# avraic.net
KiCad netlist of a schematic drawn in EAGLE
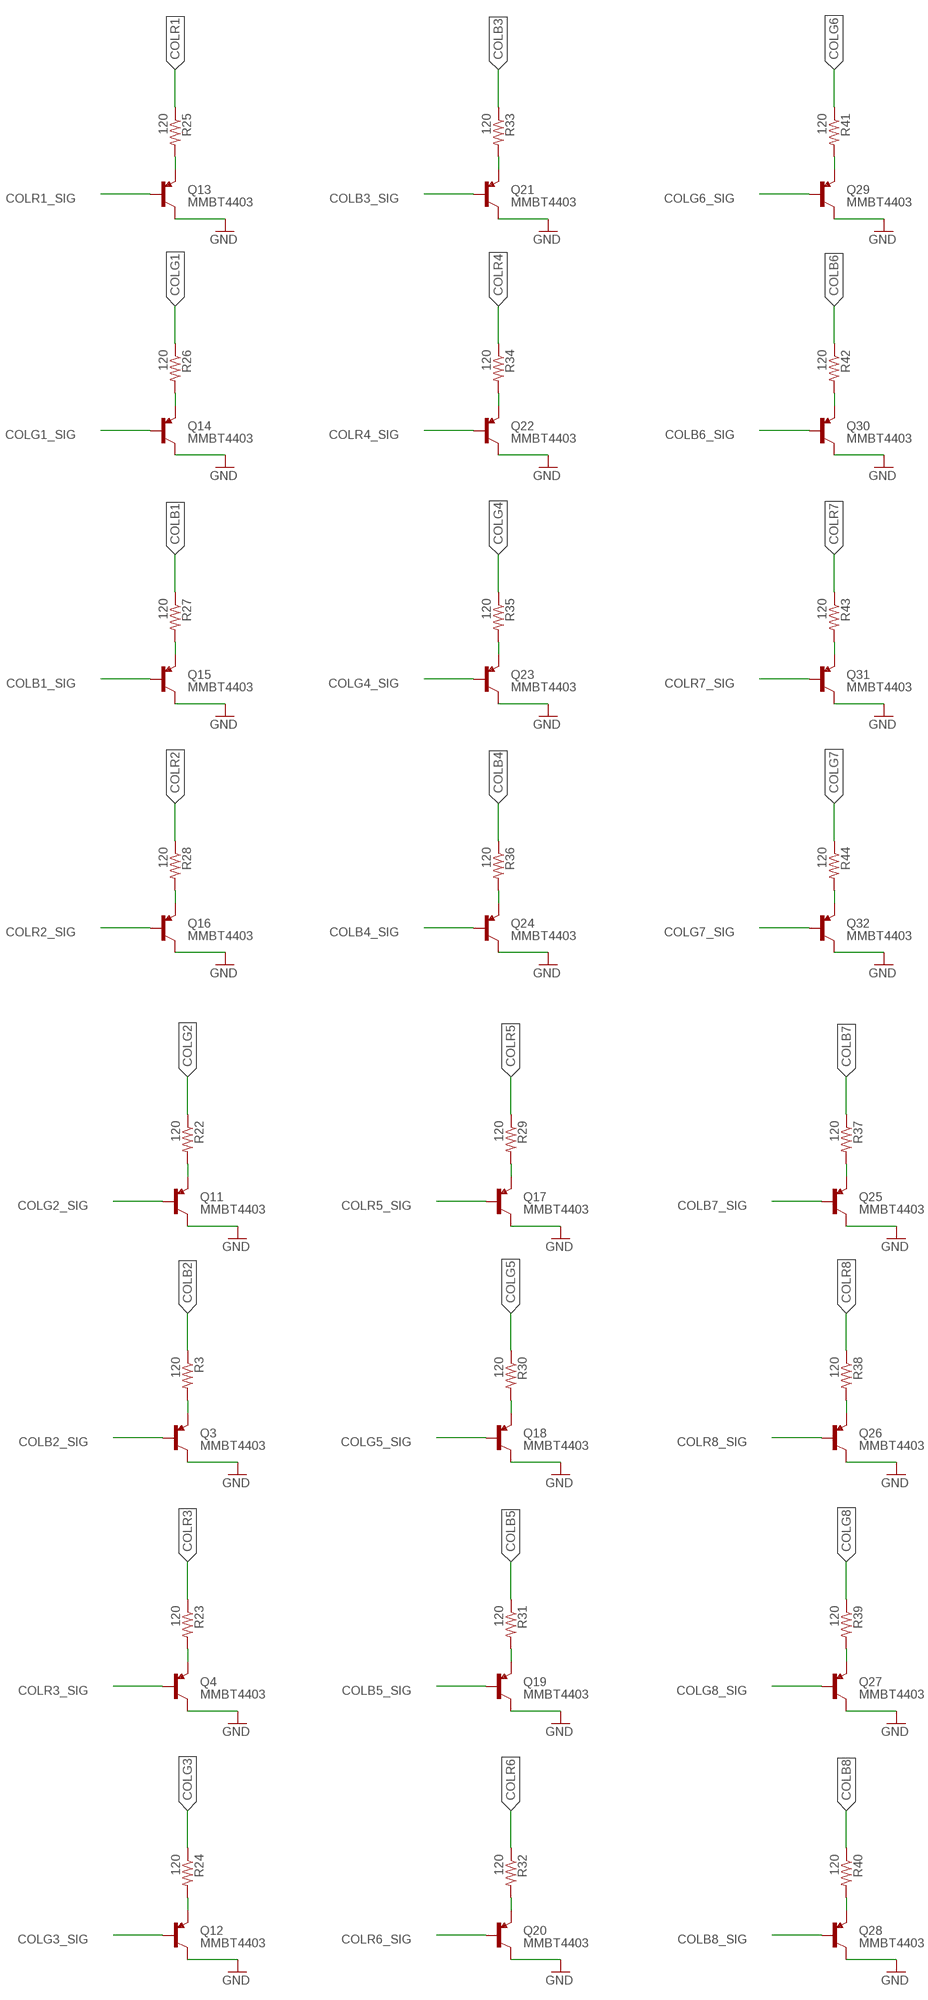
[diagram p0: schematic, sheet 1, part 1 of 3]
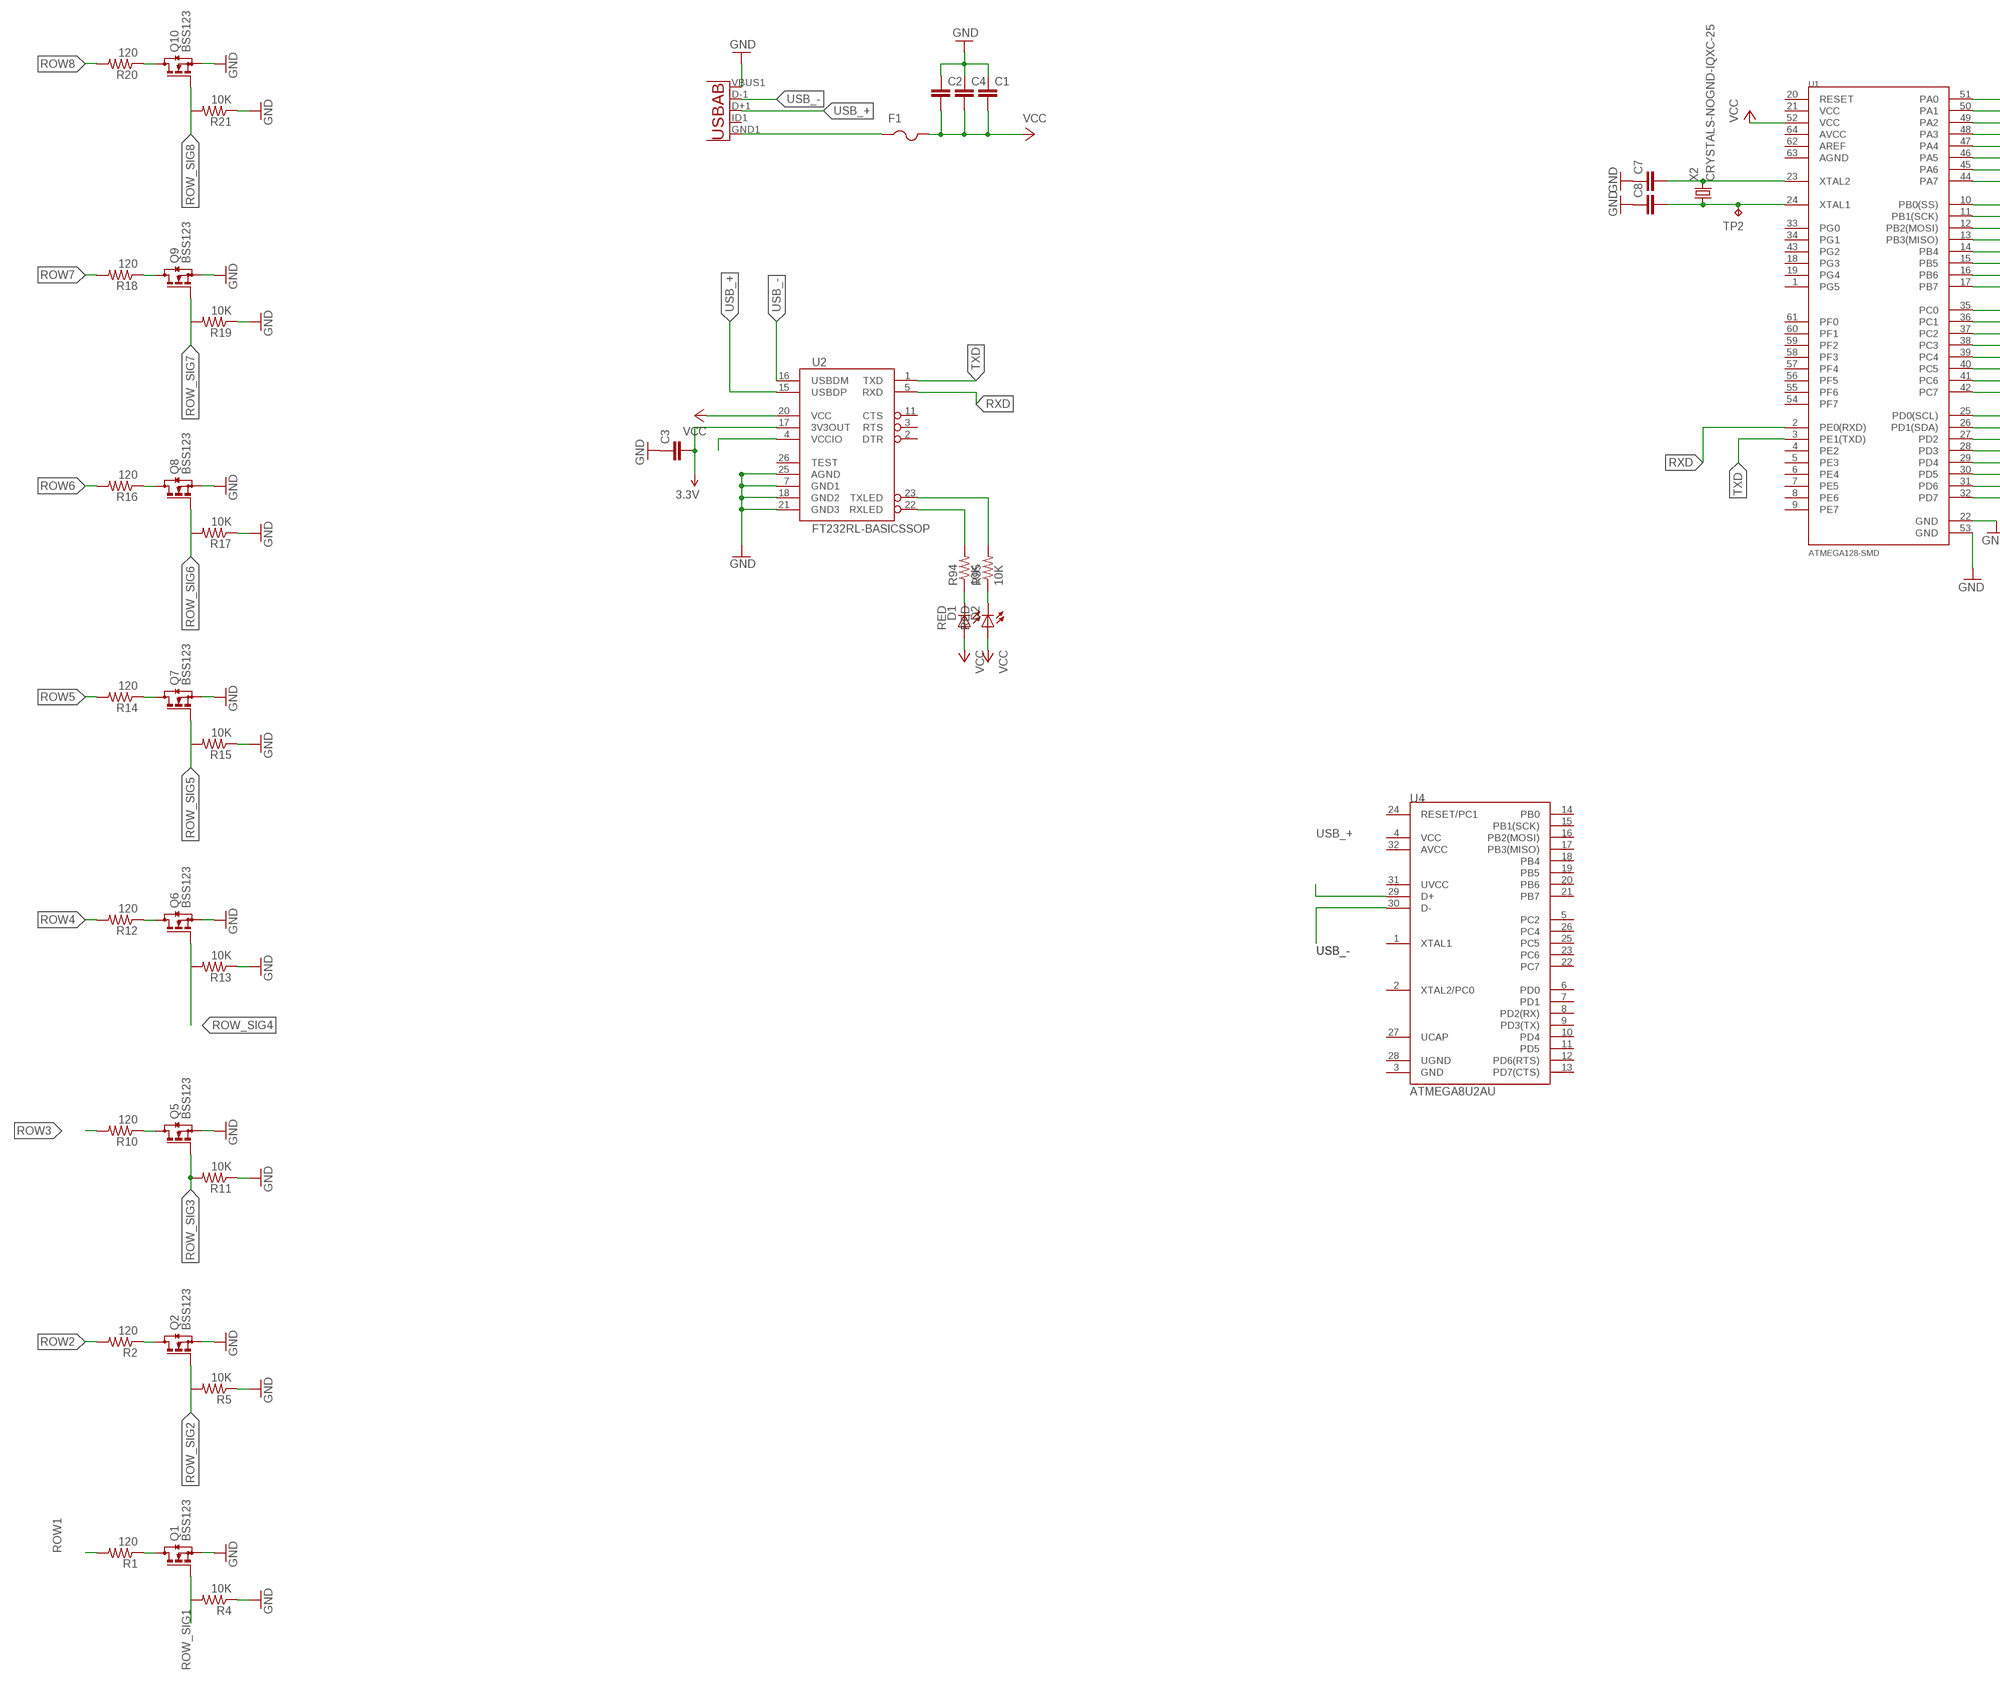
[diagram p1: schematic, sheet 1, part 2 of 3]
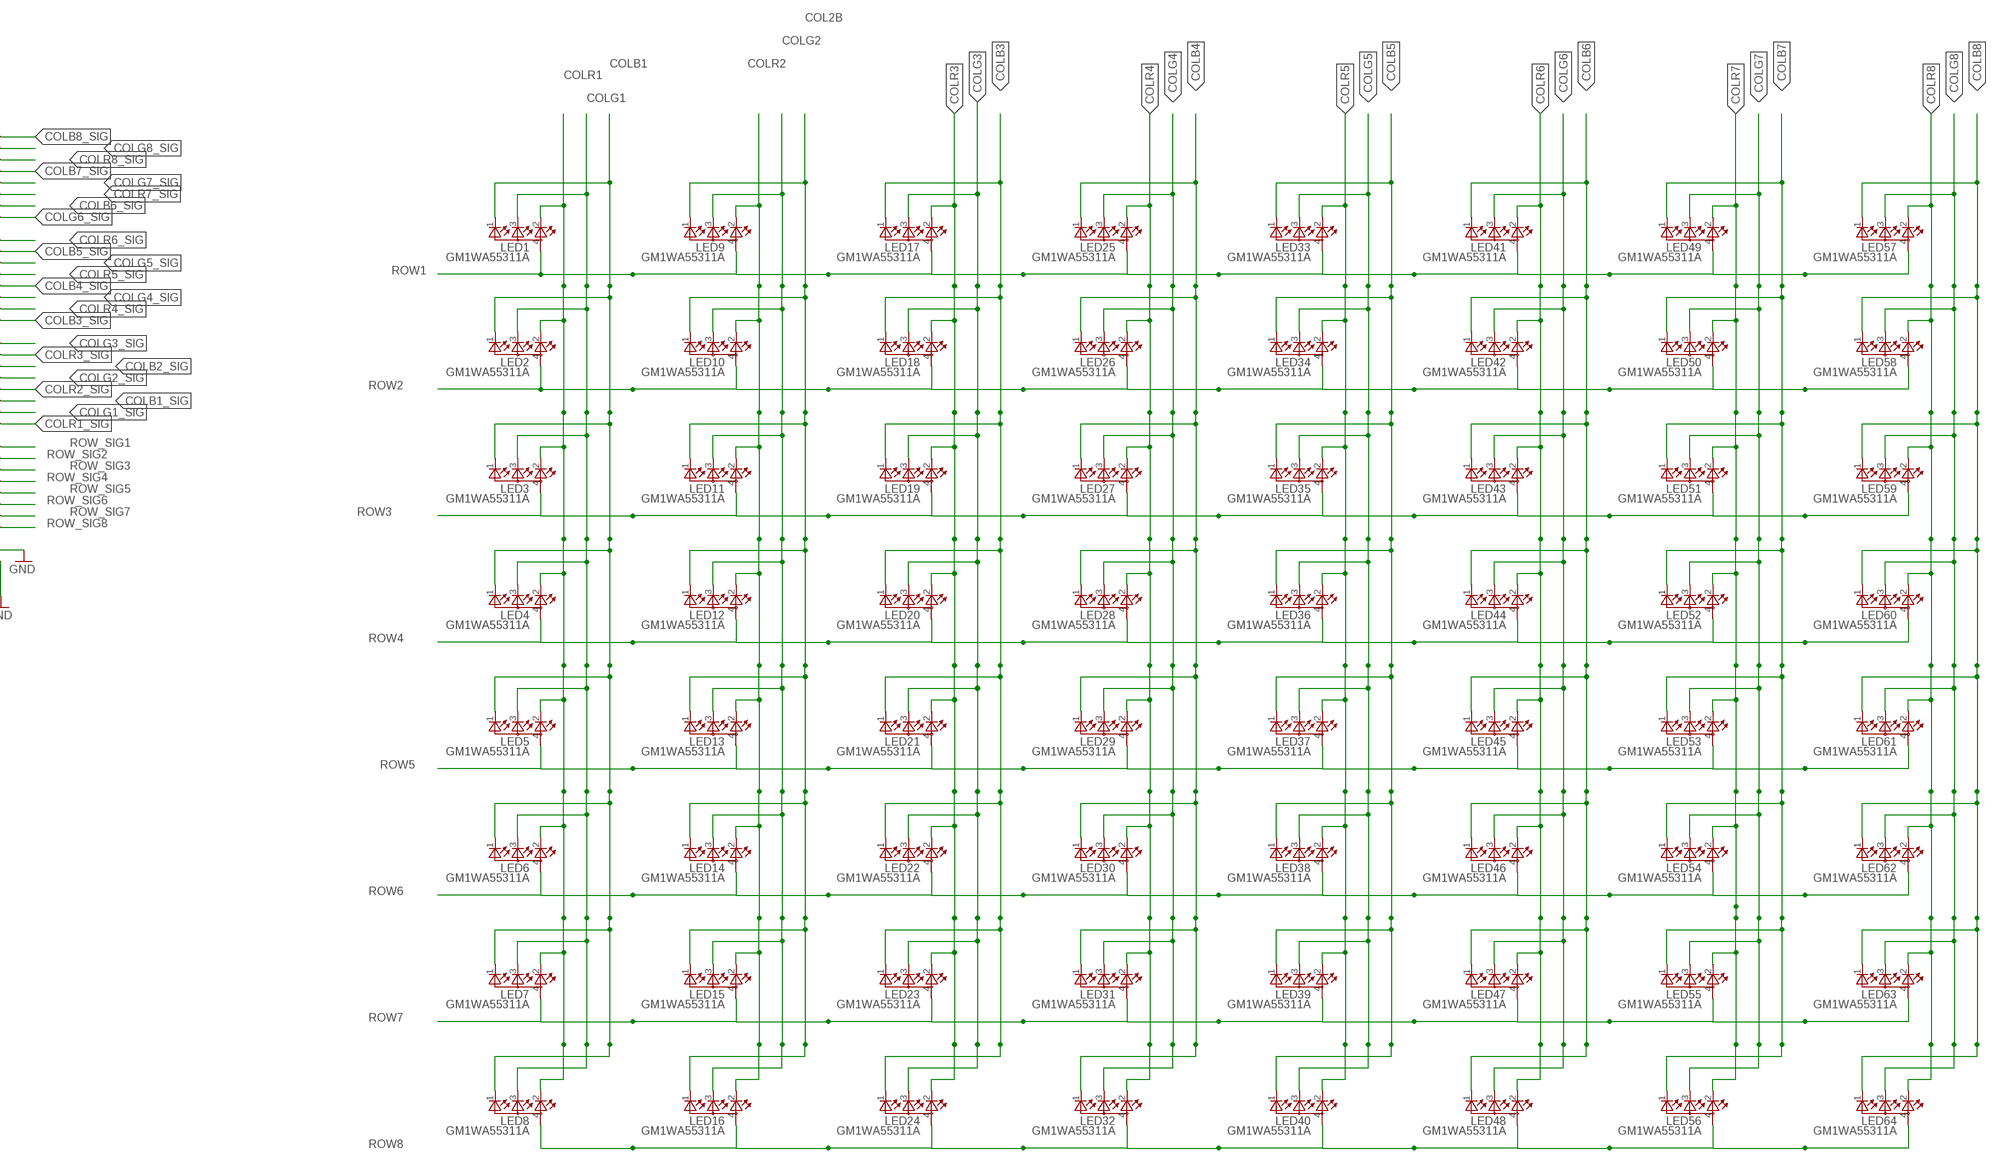
[diagram p2: schematic, sheet 1, part 3 of 3]

(export (version "E")
  (design (tool "Eeschema 10.0.6"))
  (components
    (comp (ref "C1")
      (value "C-EUC0201")
      (footprint "eagle-import:C0201")
      (libsource (lib "eagle-import") (part "C-EUC0201"))
    )
    (comp (ref "C2")
      (value "C-EUC0201")
      (footprint "eagle-import:C0201")
      (libsource (lib "eagle-import") (part "C-EUC0201"))
    )
    (comp (ref "C3")
      (value "C-EUC0402K")
      (footprint "eagle-import:C0402K")
      (libsource (lib "eagle-import") (part "C-EUC0402K"))
    )
    (comp (ref "C4")
      (value "C-EUC0201")
      (footprint "eagle-import:C0201")
      (libsource (lib "eagle-import") (part "C-EUC0201"))
    )
    (comp (ref "C7")
      (value "C-EUC0402K")
      (footprint "eagle-import:C0402K")
      (libsource (lib "eagle-import") (part "C-EUC0402K"))
    )
    (comp (ref "C8")
      (value "C-EUC0402K")
      (footprint "eagle-import:C0402K")
      (libsource (lib "eagle-import") (part "C-EUC0402K"))
    )
    (comp (ref "D1")
      (value "RED")
      (footprint "eagle-import:CHIP-LED0603")
      (libsource (lib "eagle-import") (part "LEDCHIP-LED0603"))
    )
    (comp (ref "D2")
      (value "RED")
      (footprint "eagle-import:CHIP-LED0603")
      (libsource (lib "eagle-import") (part "LEDCHIP-LED0603"))
    )
    (comp (ref "F1")
      (value "PTCFUSE-1206")
      (footprint "eagle-import:R1206")
      (libsource (lib "eagle-import") (part "PTCFUSE-1206"))
    )
    (comp (ref "LED1")
      (value "GM1WA55311A")
      (footprint "eagle-import:GM1WA55311A")
      (libsource (lib "eagle-import") (part "GM1WA55311A"))
    )
    (comp (ref "LED2")
      (value "GM1WA55311A")
      (footprint "eagle-import:GM1WA55311A")
      (libsource (lib "eagle-import") (part "GM1WA55311A"))
    )
    (comp (ref "LED3")
      (value "GM1WA55311A")
      (footprint "eagle-import:GM1WA55311A")
      (libsource (lib "eagle-import") (part "GM1WA55311A"))
    )
    (comp (ref "LED4")
      (value "GM1WA55311A")
      (footprint "eagle-import:GM1WA55311A")
      (libsource (lib "eagle-import") (part "GM1WA55311A"))
    )
    (comp (ref "LED5")
      (value "GM1WA55311A")
      (footprint "eagle-import:GM1WA55311A")
      (libsource (lib "eagle-import") (part "GM1WA55311A"))
    )
    (comp (ref "LED6")
      (value "GM1WA55311A")
      (footprint "eagle-import:GM1WA55311A")
      (libsource (lib "eagle-import") (part "GM1WA55311A"))
    )
    (comp (ref "LED7")
      (value "GM1WA55311A")
      (footprint "eagle-import:GM1WA55311A")
      (libsource (lib "eagle-import") (part "GM1WA55311A"))
    )
    (comp (ref "LED8")
      (value "GM1WA55311A")
      (footprint "eagle-import:GM1WA55311A")
      (libsource (lib "eagle-import") (part "GM1WA55311A"))
    )
    (comp (ref "LED9")
      (value "GM1WA55311A")
      (footprint "eagle-import:GM1WA55311A")
      (libsource (lib "eagle-import") (part "GM1WA55311A"))
    )
    (comp (ref "LED10")
      (value "GM1WA55311A")
      (footprint "eagle-import:GM1WA55311A")
      (libsource (lib "eagle-import") (part "GM1WA55311A"))
    )
    (comp (ref "LED11")
      (value "GM1WA55311A")
      (footprint "eagle-import:GM1WA55311A")
      (libsource (lib "eagle-import") (part "GM1WA55311A"))
    )
    (comp (ref "LED12")
      (value "GM1WA55311A")
      (footprint "eagle-import:GM1WA55311A")
      (libsource (lib "eagle-import") (part "GM1WA55311A"))
    )
    (comp (ref "LED13")
      (value "GM1WA55311A")
      (footprint "eagle-import:GM1WA55311A")
      (libsource (lib "eagle-import") (part "GM1WA55311A"))
    )
    (comp (ref "LED14")
      (value "GM1WA55311A")
      (footprint "eagle-import:GM1WA55311A")
      (libsource (lib "eagle-import") (part "GM1WA55311A"))
    )
    (comp (ref "LED15")
      (value "GM1WA55311A")
      (footprint "eagle-import:GM1WA55311A")
      (libsource (lib "eagle-import") (part "GM1WA55311A"))
    )
    (comp (ref "LED16")
      (value "GM1WA55311A")
      (footprint "eagle-import:GM1WA55311A")
      (libsource (lib "eagle-import") (part "GM1WA55311A"))
    )
    (comp (ref "LED17")
      (value "GM1WA55311A")
      (footprint "eagle-import:GM1WA55311A")
      (libsource (lib "eagle-import") (part "GM1WA55311A"))
    )
    (comp (ref "LED18")
      (value "GM1WA55311A")
      (footprint "eagle-import:GM1WA55311A")
      (libsource (lib "eagle-import") (part "GM1WA55311A"))
    )
    (comp (ref "LED19")
      (value "GM1WA55311A")
      (footprint "eagle-import:GM1WA55311A")
      (libsource (lib "eagle-import") (part "GM1WA55311A"))
    )
    (comp (ref "LED20")
      (value "GM1WA55311A")
      (footprint "eagle-import:GM1WA55311A")
      (libsource (lib "eagle-import") (part "GM1WA55311A"))
    )
    (comp (ref "LED21")
      (value "GM1WA55311A")
      (footprint "eagle-import:GM1WA55311A")
      (libsource (lib "eagle-import") (part "GM1WA55311A"))
    )
    (comp (ref "LED22")
      (value "GM1WA55311A")
      (footprint "eagle-import:GM1WA55311A")
      (libsource (lib "eagle-import") (part "GM1WA55311A"))
    )
    (comp (ref "LED23")
      (value "GM1WA55311A")
      (footprint "eagle-import:GM1WA55311A")
      (libsource (lib "eagle-import") (part "GM1WA55311A"))
    )
    (comp (ref "LED24")
      (value "GM1WA55311A")
      (footprint "eagle-import:GM1WA55311A")
      (libsource (lib "eagle-import") (part "GM1WA55311A"))
    )
    (comp (ref "LED25")
      (value "GM1WA55311A")
      (footprint "eagle-import:GM1WA55311A")
      (libsource (lib "eagle-import") (part "GM1WA55311A"))
    )
    (comp (ref "LED26")
      (value "GM1WA55311A")
      (footprint "eagle-import:GM1WA55311A")
      (libsource (lib "eagle-import") (part "GM1WA55311A"))
    )
    (comp (ref "LED27")
      (value "GM1WA55311A")
      (footprint "eagle-import:GM1WA55311A")
      (libsource (lib "eagle-import") (part "GM1WA55311A"))
    )
    (comp (ref "LED28")
      (value "GM1WA55311A")
      (footprint "eagle-import:GM1WA55311A")
      (libsource (lib "eagle-import") (part "GM1WA55311A"))
    )
    (comp (ref "LED29")
      (value "GM1WA55311A")
      (footprint "eagle-import:GM1WA55311A")
      (libsource (lib "eagle-import") (part "GM1WA55311A"))
    )
    (comp (ref "LED30")
      (value "GM1WA55311A")
      (footprint "eagle-import:GM1WA55311A")
      (libsource (lib "eagle-import") (part "GM1WA55311A"))
    )
    (comp (ref "LED31")
      (value "GM1WA55311A")
      (footprint "eagle-import:GM1WA55311A")
      (libsource (lib "eagle-import") (part "GM1WA55311A"))
    )
    (comp (ref "LED32")
      (value "GM1WA55311A")
      (footprint "eagle-import:GM1WA55311A")
      (libsource (lib "eagle-import") (part "GM1WA55311A"))
    )
    (comp (ref "LED33")
      (value "GM1WA55311A")
      (footprint "eagle-import:GM1WA55311A")
      (libsource (lib "eagle-import") (part "GM1WA55311A"))
    )
    (comp (ref "LED34")
      (value "GM1WA55311A")
      (footprint "eagle-import:GM1WA55311A")
      (libsource (lib "eagle-import") (part "GM1WA55311A"))
    )
    (comp (ref "LED35")
      (value "GM1WA55311A")
      (footprint "eagle-import:GM1WA55311A")
      (libsource (lib "eagle-import") (part "GM1WA55311A"))
    )
    (comp (ref "LED36")
      (value "GM1WA55311A")
      (footprint "eagle-import:GM1WA55311A")
      (libsource (lib "eagle-import") (part "GM1WA55311A"))
    )
    (comp (ref "LED37")
      (value "GM1WA55311A")
      (footprint "eagle-import:GM1WA55311A")
      (libsource (lib "eagle-import") (part "GM1WA55311A"))
    )
    (comp (ref "LED38")
      (value "GM1WA55311A")
      (footprint "eagle-import:GM1WA55311A")
      (libsource (lib "eagle-import") (part "GM1WA55311A"))
    )
    (comp (ref "LED39")
      (value "GM1WA55311A")
      (footprint "eagle-import:GM1WA55311A")
      (libsource (lib "eagle-import") (part "GM1WA55311A"))
    )
    (comp (ref "LED40")
      (value "GM1WA55311A")
      (footprint "eagle-import:GM1WA55311A")
      (libsource (lib "eagle-import") (part "GM1WA55311A"))
    )
    (comp (ref "LED41")
      (value "GM1WA55311A")
      (footprint "eagle-import:GM1WA55311A")
      (libsource (lib "eagle-import") (part "GM1WA55311A"))
    )
    (comp (ref "LED42")
      (value "GM1WA55311A")
      (footprint "eagle-import:GM1WA55311A")
      (libsource (lib "eagle-import") (part "GM1WA55311A"))
    )
    (comp (ref "LED43")
      (value "GM1WA55311A")
      (footprint "eagle-import:GM1WA55311A")
      (libsource (lib "eagle-import") (part "GM1WA55311A"))
    )
    (comp (ref "LED44")
      (value "GM1WA55311A")
      (footprint "eagle-import:GM1WA55311A")
      (libsource (lib "eagle-import") (part "GM1WA55311A"))
    )
    (comp (ref "LED45")
      (value "GM1WA55311A")
      (footprint "eagle-import:GM1WA55311A")
      (libsource (lib "eagle-import") (part "GM1WA55311A"))
    )
    (comp (ref "LED46")
      (value "GM1WA55311A")
      (footprint "eagle-import:GM1WA55311A")
      (libsource (lib "eagle-import") (part "GM1WA55311A"))
    )
    (comp (ref "LED47")
      (value "GM1WA55311A")
      (footprint "eagle-import:GM1WA55311A")
      (libsource (lib "eagle-import") (part "GM1WA55311A"))
    )
    (comp (ref "LED48")
      (value "GM1WA55311A")
      (footprint "eagle-import:GM1WA55311A")
      (libsource (lib "eagle-import") (part "GM1WA55311A"))
    )
    (comp (ref "LED49")
      (value "GM1WA55311A")
      (footprint "eagle-import:GM1WA55311A")
      (libsource (lib "eagle-import") (part "GM1WA55311A"))
    )
    (comp (ref "LED50")
      (value "GM1WA55311A")
      (footprint "eagle-import:GM1WA55311A")
      (libsource (lib "eagle-import") (part "GM1WA55311A"))
    )
    (comp (ref "LED51")
      (value "GM1WA55311A")
      (footprint "eagle-import:GM1WA55311A")
      (libsource (lib "eagle-import") (part "GM1WA55311A"))
    )
    (comp (ref "LED52")
      (value "GM1WA55311A")
      (footprint "eagle-import:GM1WA55311A")
      (libsource (lib "eagle-import") (part "GM1WA55311A"))
    )
    (comp (ref "LED53")
      (value "GM1WA55311A")
      (footprint "eagle-import:GM1WA55311A")
      (libsource (lib "eagle-import") (part "GM1WA55311A"))
    )
    (comp (ref "LED54")
      (value "GM1WA55311A")
      (footprint "eagle-import:GM1WA55311A")
      (libsource (lib "eagle-import") (part "GM1WA55311A"))
    )
    (comp (ref "LED55")
      (value "GM1WA55311A")
      (footprint "eagle-import:GM1WA55311A")
      (libsource (lib "eagle-import") (part "GM1WA55311A"))
    )
    (comp (ref "LED56")
      (value "GM1WA55311A")
      (footprint "eagle-import:GM1WA55311A")
      (libsource (lib "eagle-import") (part "GM1WA55311A"))
    )
    (comp (ref "LED57")
      (value "GM1WA55311A")
      (footprint "eagle-import:GM1WA55311A")
      (libsource (lib "eagle-import") (part "GM1WA55311A"))
    )
    (comp (ref "LED58")
      (value "GM1WA55311A")
      (footprint "eagle-import:GM1WA55311A")
      (libsource (lib "eagle-import") (part "GM1WA55311A"))
    )
    (comp (ref "LED59")
      (value "GM1WA55311A")
      (footprint "eagle-import:GM1WA55311A")
      (libsource (lib "eagle-import") (part "GM1WA55311A"))
    )
    (comp (ref "LED60")
      (value "GM1WA55311A")
      (footprint "eagle-import:GM1WA55311A")
      (libsource (lib "eagle-import") (part "GM1WA55311A"))
    )
    (comp (ref "LED61")
      (value "GM1WA55311A")
      (footprint "eagle-import:GM1WA55311A")
      (libsource (lib "eagle-import") (part "GM1WA55311A"))
    )
    (comp (ref "LED62")
      (value "GM1WA55311A")
      (footprint "eagle-import:GM1WA55311A")
      (libsource (lib "eagle-import") (part "GM1WA55311A"))
    )
    (comp (ref "LED63")
      (value "GM1WA55311A")
      (footprint "eagle-import:GM1WA55311A")
      (libsource (lib "eagle-import") (part "GM1WA55311A"))
    )
    (comp (ref "LED64")
      (value "GM1WA55311A")
      (footprint "eagle-import:GM1WA55311A")
      (libsource (lib "eagle-import") (part "GM1WA55311A"))
    )
    (comp (ref "Q1")
      (value "BSS123")
      (footprint "eagle-import:SOT23")
      (libsource (lib "eagle-import") (part "BSS123"))
    )
    (comp (ref "Q2")
      (value "BSS123")
      (footprint "eagle-import:SOT23")
      (libsource (lib "eagle-import") (part "BSS123"))
    )
    (comp (ref "Q3")
      (value "MMBT4403")
      (footprint "eagle-import:SOT23-3")
      (libsource (lib "eagle-import") (part "TRANSISTOR_PNPMMBT4403"))
    )
    (comp (ref "Q4")
      (value "MMBT4403")
      (footprint "eagle-import:SOT23-3")
      (libsource (lib "eagle-import") (part "TRANSISTOR_PNPMMBT4403"))
    )
    (comp (ref "Q5")
      (value "BSS123")
      (footprint "eagle-import:SOT23")
      (libsource (lib "eagle-import") (part "BSS123"))
    )
    (comp (ref "Q6")
      (value "BSS123")
      (footprint "eagle-import:SOT23")
      (libsource (lib "eagle-import") (part "BSS123"))
    )
    (comp (ref "Q7")
      (value "BSS123")
      (footprint "eagle-import:SOT23")
      (libsource (lib "eagle-import") (part "BSS123"))
    )
    (comp (ref "Q8")
      (value "BSS123")
      (footprint "eagle-import:SOT23")
      (libsource (lib "eagle-import") (part "BSS123"))
    )
    (comp (ref "Q9")
      (value "BSS123")
      (footprint "eagle-import:SOT23")
      (libsource (lib "eagle-import") (part "BSS123"))
    )
    (comp (ref "Q10")
      (value "BSS123")
      (footprint "eagle-import:SOT23")
      (libsource (lib "eagle-import") (part "BSS123"))
    )
    (comp (ref "Q11")
      (value "MMBT4403")
      (footprint "eagle-import:SOT23-3")
      (libsource (lib "eagle-import") (part "TRANSISTOR_PNPMMBT4403"))
    )
    (comp (ref "Q12")
      (value "MMBT4403")
      (footprint "eagle-import:SOT23-3")
      (libsource (lib "eagle-import") (part "TRANSISTOR_PNPMMBT4403"))
    )
    (comp (ref "Q13")
      (value "MMBT4403")
      (footprint "eagle-import:SOT23-3")
      (libsource (lib "eagle-import") (part "TRANSISTOR_PNPMMBT4403"))
    )
    (comp (ref "Q14")
      (value "MMBT4403")
      (footprint "eagle-import:SOT23-3")
      (libsource (lib "eagle-import") (part "TRANSISTOR_PNPMMBT4403"))
    )
    (comp (ref "Q15")
      (value "MMBT4403")
      (footprint "eagle-import:SOT23-3")
      (libsource (lib "eagle-import") (part "TRANSISTOR_PNPMMBT4403"))
    )
    (comp (ref "Q16")
      (value "MMBT4403")
      (footprint "eagle-import:SOT23-3")
      (libsource (lib "eagle-import") (part "TRANSISTOR_PNPMMBT4403"))
    )
    (comp (ref "Q17")
      (value "MMBT4403")
      (footprint "eagle-import:SOT23-3")
      (libsource (lib "eagle-import") (part "TRANSISTOR_PNPMMBT4403"))
    )
    (comp (ref "Q18")
      (value "MMBT4403")
      (footprint "eagle-import:SOT23-3")
      (libsource (lib "eagle-import") (part "TRANSISTOR_PNPMMBT4403"))
    )
    (comp (ref "Q19")
      (value "MMBT4403")
      (footprint "eagle-import:SOT23-3")
      (libsource (lib "eagle-import") (part "TRANSISTOR_PNPMMBT4403"))
    )
    (comp (ref "Q20")
      (value "MMBT4403")
      (footprint "eagle-import:SOT23-3")
      (libsource (lib "eagle-import") (part "TRANSISTOR_PNPMMBT4403"))
    )
    (comp (ref "Q21")
      (value "MMBT4403")
      (footprint "eagle-import:SOT23-3")
      (libsource (lib "eagle-import") (part "TRANSISTOR_PNPMMBT4403"))
    )
    (comp (ref "Q22")
      (value "MMBT4403")
      (footprint "eagle-import:SOT23-3")
      (libsource (lib "eagle-import") (part "TRANSISTOR_PNPMMBT4403"))
    )
    (comp (ref "Q23")
      (value "MMBT4403")
      (footprint "eagle-import:SOT23-3")
      (libsource (lib "eagle-import") (part "TRANSISTOR_PNPMMBT4403"))
    )
    (comp (ref "Q24")
      (value "MMBT4403")
      (footprint "eagle-import:SOT23-3")
      (libsource (lib "eagle-import") (part "TRANSISTOR_PNPMMBT4403"))
    )
    (comp (ref "Q25")
      (value "MMBT4403")
      (footprint "eagle-import:SOT23-3")
      (libsource (lib "eagle-import") (part "TRANSISTOR_PNPMMBT4403"))
    )
    (comp (ref "Q26")
      (value "MMBT4403")
      (footprint "eagle-import:SOT23-3")
      (libsource (lib "eagle-import") (part "TRANSISTOR_PNPMMBT4403"))
    )
    (comp (ref "Q27")
      (value "MMBT4403")
      (footprint "eagle-import:SOT23-3")
      (libsource (lib "eagle-import") (part "TRANSISTOR_PNPMMBT4403"))
    )
    (comp (ref "Q28")
      (value "MMBT4403")
      (footprint "eagle-import:SOT23-3")
      (libsource (lib "eagle-import") (part "TRANSISTOR_PNPMMBT4403"))
    )
    (comp (ref "Q29")
      (value "MMBT4403")
      (footprint "eagle-import:SOT23-3")
      (libsource (lib "eagle-import") (part "TRANSISTOR_PNPMMBT4403"))
    )
    (comp (ref "Q30")
      (value "MMBT4403")
      (footprint "eagle-import:SOT23-3")
      (libsource (lib "eagle-import") (part "TRANSISTOR_PNPMMBT4403"))
    )
    (comp (ref "Q31")
      (value "MMBT4403")
      (footprint "eagle-import:SOT23-3")
      (libsource (lib "eagle-import") (part "TRANSISTOR_PNPMMBT4403"))
    )
    (comp (ref "Q32")
      (value "MMBT4403")
      (footprint "eagle-import:SOT23-3")
      (libsource (lib "eagle-import") (part "TRANSISTOR_PNPMMBT4403"))
    )
    (comp (ref "R1")
      (value "120")
      (footprint "eagle-import:0603-RES")
      (libsource (lib "eagle-import") (part "RESISTOR0603-RES"))
    )
    (comp (ref "R2")
      (value "120")
      (footprint "eagle-import:0603-RES")
      (libsource (lib "eagle-import") (part "RESISTOR0603-RES"))
    )
    (comp (ref "R3")
      (value "120")
      (footprint "eagle-import:MINI_MELF-0102R")
      (libsource (lib "eagle-import") (part "R-US_MELF0102R"))
    )
    (comp (ref "R4")
      (value "10K")
      (footprint "eagle-import:0603-RES")
      (libsource (lib "eagle-import") (part "RESISTOR0603-RES"))
    )
    (comp (ref "R5")
      (value "10K")
      (footprint "eagle-import:0603-RES")
      (libsource (lib "eagle-import") (part "RESISTOR0603-RES"))
    )
    (comp (ref "R10")
      (value "120")
      (footprint "eagle-import:0603-RES")
      (libsource (lib "eagle-import") (part "RESISTOR0603-RES"))
    )
    (comp (ref "R11")
      (value "10K")
      (footprint "eagle-import:0603-RES")
      (libsource (lib "eagle-import") (part "RESISTOR0603-RES"))
    )
    (comp (ref "R12")
      (value "120")
      (footprint "eagle-import:0603-RES")
      (libsource (lib "eagle-import") (part "RESISTOR0603-RES"))
    )
    (comp (ref "R13")
      (value "10K")
      (footprint "eagle-import:0603-RES")
      (libsource (lib "eagle-import") (part "RESISTOR0603-RES"))
    )
    (comp (ref "R14")
      (value "120")
      (footprint "eagle-import:0603-RES")
      (libsource (lib "eagle-import") (part "RESISTOR0603-RES"))
    )
    (comp (ref "R15")
      (value "10K")
      (footprint "eagle-import:0603-RES")
      (libsource (lib "eagle-import") (part "RESISTOR0603-RES"))
    )
    (comp (ref "R16")
      (value "120")
      (footprint "eagle-import:0603-RES")
      (libsource (lib "eagle-import") (part "RESISTOR0603-RES"))
    )
    (comp (ref "R17")
      (value "10K")
      (footprint "eagle-import:0603-RES")
      (libsource (lib "eagle-import") (part "RESISTOR0603-RES"))
    )
    (comp (ref "R18")
      (value "120")
      (footprint "eagle-import:0603-RES")
      (libsource (lib "eagle-import") (part "RESISTOR0603-RES"))
    )
    (comp (ref "R19")
      (value "10K")
      (footprint "eagle-import:0603-RES")
      (libsource (lib "eagle-import") (part "RESISTOR0603-RES"))
    )
    (comp (ref "R20")
      (value "120")
      (footprint "eagle-import:0603-RES")
      (libsource (lib "eagle-import") (part "RESISTOR0603-RES"))
    )
    (comp (ref "R21")
      (value "10K")
      (footprint "eagle-import:0603-RES")
      (libsource (lib "eagle-import") (part "RESISTOR0603-RES"))
    )
    (comp (ref "R22")
      (value "120")
      (footprint "eagle-import:MINI_MELF-0102R")
      (libsource (lib "eagle-import") (part "R-US_MELF0102R"))
    )
    (comp (ref "R23")
      (value "120")
      (footprint "eagle-import:MINI_MELF-0102R")
      (libsource (lib "eagle-import") (part "R-US_MELF0102R"))
    )
    (comp (ref "R24")
      (value "120")
      (footprint "eagle-import:0603-RES")
      (libsource (lib "eagle-import") (part "RESISTOR0603-RES"))
    )
    (comp (ref "R25")
      (value "120")
      (footprint "eagle-import:0603-RES")
      (libsource (lib "eagle-import") (part "RESISTOR0603-RES"))
    )
    (comp (ref "R26")
      (value "120")
      (footprint "eagle-import:MINI_MELF-0102R")
      (libsource (lib "eagle-import") (part "R-US_MELF0102R"))
    )
    (comp (ref "R27")
      (value "120")
      (footprint "eagle-import:MINI_MELF-0102R")
      (libsource (lib "eagle-import") (part "R-US_MELF0102R"))
    )
    (comp (ref "R28")
      (value "120")
      (footprint "eagle-import:MINI_MELF-0102R")
      (libsource (lib "eagle-import") (part "R-US_MELF0102R"))
    )
    (comp (ref "R29")
      (value "120")
      (footprint "eagle-import:MINI_MELF-0102R")
      (libsource (lib "eagle-import") (part "R-US_MELF0102R"))
    )
    (comp (ref "R30")
      (value "120")
      (footprint "eagle-import:0603-RES")
      (libsource (lib "eagle-import") (part "RESISTOR0603-RES"))
    )
    (comp (ref "R31")
      (value "120")
      (footprint "eagle-import:0603-RES")
      (libsource (lib "eagle-import") (part "RESISTOR0603-RES"))
    )
    (comp (ref "R32")
      (value "120")
      (footprint "eagle-import:0603-RES")
      (libsource (lib "eagle-import") (part "RESISTOR0603-RES"))
    )
    (comp (ref "R33")
      (value "120")
      (footprint "eagle-import:MINI_MELF-0102R")
      (libsource (lib "eagle-import") (part "R-US_MELF0102R"))
    )
    (comp (ref "R34")
      (value "120")
      (footprint "eagle-import:MINI_MELF-0102R")
      (libsource (lib "eagle-import") (part "R-US_MELF0102R"))
    )
    (comp (ref "R35")
      (value "120")
      (footprint "eagle-import:MINI_MELF-0102R")
      (libsource (lib "eagle-import") (part "R-US_MELF0102R"))
    )
    (comp (ref "R36")
      (value "120")
      (footprint "eagle-import:MINI_MELF-0102R")
      (libsource (lib "eagle-import") (part "R-US_MELF0102R"))
    )
    (comp (ref "R37")
      (value "120")
      (footprint "eagle-import:MINI_MELF-0102R")
      (libsource (lib "eagle-import") (part "R-US_MELF0102R"))
    )
    (comp (ref "R38")
      (value "120")
      (footprint "eagle-import:MINI_MELF-0102R")
      (libsource (lib "eagle-import") (part "R-US_MELF0102R"))
    )
    (comp (ref "R39")
      (value "120")
      (footprint "eagle-import:MINI_MELF-0102R")
      (libsource (lib "eagle-import") (part "R-US_MELF0102R"))
    )
    (comp (ref "R40")
      (value "120")
      (footprint "eagle-import:MINI_MELF-0102R")
      (libsource (lib "eagle-import") (part "R-US_MELF0102R"))
    )
    (comp (ref "R41")
      (value "120")
      (footprint "eagle-import:MINI_MELF-0102R")
      (libsource (lib "eagle-import") (part "R-US_MELF0102R"))
    )
    (comp (ref "R42")
      (value "120")
      (footprint "eagle-import:MINI_MELF-0102R")
      (libsource (lib "eagle-import") (part "R-US_MELF0102R"))
    )
    (comp (ref "R43")
      (value "120")
      (footprint "eagle-import:MINI_MELF-0102R")
      (libsource (lib "eagle-import") (part "R-US_MELF0102R"))
    )
    (comp (ref "R44")
      (value "120")
      (footprint "eagle-import:MINI_MELF-0102R")
      (libsource (lib "eagle-import") (part "R-US_MELF0102R"))
    )
    (comp (ref "R94")
      (value "10K")
      (footprint "eagle-import:0603-RES")
      (libsource (lib "eagle-import") (part "RESISTOR0603-RES"))
    )
    (comp (ref "R95")
      (value "10K")
      (footprint "eagle-import:0603-RES")
      (libsource (lib "eagle-import") (part "RESISTOR0603-RES"))
    )
    (comp (ref "TP2")
      (value "TPB1,27")
      (footprint "eagle-import:B1,27")
      (libsource (lib "eagle-import") (part "TPB1,27"))
    )
    (comp (ref "U1")
      (value "ATMEGA128-SMD")
      (footprint "eagle-import:TQFP64_14X14MM")
      (libsource (lib "eagle-import") (part "ATMEGA128-SMD"))
    )
    (comp (ref "U2")
      (value "FT232RL-BASICSSOP")
      (footprint "eagle-import:SSOP28DB")
      (libsource (lib "eagle-import") (part "FT232RL-BASICSSOP"))
    )
    (comp (ref "U3")
      (value "USB\"\"")
      (footprint "eagle-import:USB-MICRO-SMD")
      (libsource (lib "eagle-import") (part "USB{dblquote}{dblquote}"))
    )
    (comp (ref "U4")
      (value "ATMEGA8U2AU")
      (footprint "eagle-import:TQFP32-08")
      (libsource (lib "eagle-import") (part "ATMEGA8U2AU"))
    )
    (comp (ref "X2")
      (value "CRYSTALS-NOGND-IQXC-25")
      (footprint "eagle-import:2.0X1.2-2PAD")
      (libsource (lib "eagle-import") (part "CRYSTALS-NOGND-IQXC-25"))
    )
  )
  (nets
    (net (code "1") (name "/COL2B") (class "Default")
      (node (ref "LED10") (pin "1") (pinfunction "CGREEN_1") (pintype "passive"))
      (node (ref "LED11") (pin "1") (pinfunction "CGREEN_1") (pintype "passive"))
      (node (ref "LED12") (pin "1") (pinfunction "CGREEN_1") (pintype "passive"))
      (node (ref "LED13") (pin "1") (pinfunction "CGREEN_1") (pintype "passive"))
      (node (ref "LED14") (pin "1") (pinfunction "CGREEN_1") (pintype "passive"))
      (node (ref "LED15") (pin "1") (pinfunction "CGREEN_1") (pintype "passive"))
      (node (ref "LED16") (pin "1") (pinfunction "CGREEN_1") (pintype "passive"))
      (node (ref "LED9") (pin "1") (pinfunction "CGREEN_1") (pintype "passive"))
    )
    (net (code "2") (name "/ROW1") (class "Default")
      (node (ref "LED1") (pin "4") (pinfunction "A_4") (pintype "passive"))
      (node (ref "LED17") (pin "4") (pinfunction "A_4") (pintype "passive"))
      (node (ref "LED25") (pin "4") (pinfunction "A_4") (pintype "passive"))
      (node (ref "LED33") (pin "4") (pinfunction "A_4") (pintype "passive"))
      (node (ref "LED41") (pin "4") (pinfunction "A_4") (pintype "passive"))
      (node (ref "LED49") (pin "4") (pinfunction "A_4") (pintype "passive"))
      (node (ref "LED57") (pin "4") (pinfunction "A_4") (pintype "passive"))
      (node (ref "LED9") (pin "4") (pinfunction "A_4") (pintype "passive"))
      (node (ref "R1") (pin "2") (pinfunction "2_2") (pintype "passive"))
    )
    (net (code "3") (name "/ROW_SIG1") (class "Default")
      (node (ref "Q1") (pin "1") (pinfunction "G_1") (pintype "passive"))
      (node (ref "R4") (pin "2") (pinfunction "2_2") (pintype "passive"))
      (node (ref "U1") (pin "25") (pinfunction "PD0(SCL)_25") (pintype "bidirectional"))
    )
    (net (code "4") (name "3.3V") (class "Default")
      (node (ref "C3") (pin "2") (pinfunction "2_2") (pintype "passive"))
      (node (ref "U2") (pin "17") (pinfunction "3V3OUT_17") (pintype "output"))
    )
    (net (code "5") (name "COLB1") (class "Default")
      (node (ref "LED1") (pin "1") (pinfunction "CGREEN_1") (pintype "passive"))
      (node (ref "LED2") (pin "1") (pinfunction "CGREEN_1") (pintype "passive"))
      (node (ref "LED3") (pin "1") (pinfunction "CGREEN_1") (pintype "passive"))
      (node (ref "LED4") (pin "1") (pinfunction "CGREEN_1") (pintype "passive"))
      (node (ref "LED5") (pin "1") (pinfunction "CGREEN_1") (pintype "passive"))
      (node (ref "LED6") (pin "1") (pinfunction "CGREEN_1") (pintype "passive"))
      (node (ref "LED7") (pin "1") (pinfunction "CGREEN_1") (pintype "passive"))
      (node (ref "LED8") (pin "1") (pinfunction "CGREEN_1") (pintype "passive"))
      (node (ref "R27") (pin "1") (pinfunction "1_1") (pintype "passive"))
    )
    (net (code "6") (name "COLB1_SIG") (class "Default")
      (node (ref "Q15") (pin "1") (pinfunction "B_1") (pintype "passive"))
      (node (ref "U1") (pin "40") (pinfunction "PC5_40") (pintype "bidirectional"))
    )
    (net (code "7") (name "COLB2") (class "Default")
      (node (ref "R3") (pin "1") (pinfunction "1_1") (pintype "passive"))
    )
    (net (code "8") (name "COLB2_SIG") (class "Default")
      (node (ref "Q3") (pin "1") (pinfunction "B_1") (pintype "passive"))
      (node (ref "U1") (pin "37") (pinfunction "PC2_37") (pintype "bidirectional"))
    )
    (net (code "9") (name "COLB3") (class "Default")
      (node (ref "LED17") (pin "1") (pinfunction "CGREEN_1") (pintype "passive"))
      (node (ref "LED18") (pin "1") (pinfunction "CGREEN_1") (pintype "passive"))
      (node (ref "LED19") (pin "1") (pinfunction "CGREEN_1") (pintype "passive"))
      (node (ref "LED20") (pin "1") (pinfunction "CGREEN_1") (pintype "passive"))
      (node (ref "LED21") (pin "1") (pinfunction "CGREEN_1") (pintype "passive"))
      (node (ref "LED22") (pin "1") (pinfunction "CGREEN_1") (pintype "passive"))
      (node (ref "LED23") (pin "1") (pinfunction "CGREEN_1") (pintype "passive"))
      (node (ref "LED24") (pin "1") (pinfunction "CGREEN_1") (pintype "passive"))
      (node (ref "R33") (pin "1") (pinfunction "1_1") (pintype "passive"))
    )
    (net (code "10") (name "COLB3_SIG") (class "Default")
      (node (ref "Q21") (pin "1") (pinfunction "B_1") (pintype "passive"))
      (node (ref "U1") (pin "17") (pinfunction "PB7_17") (pintype "bidirectional"))
    )
    (net (code "11") (name "COLB4") (class "Default")
      (node (ref "LED25") (pin "1") (pinfunction "CGREEN_1") (pintype "passive"))
      (node (ref "LED26") (pin "1") (pinfunction "CGREEN_1") (pintype "passive"))
      (node (ref "LED27") (pin "1") (pinfunction "CGREEN_1") (pintype "passive"))
      (node (ref "LED28") (pin "1") (pinfunction "CGREEN_1") (pintype "passive"))
      (node (ref "LED29") (pin "1") (pinfunction "CGREEN_1") (pintype "passive"))
      (node (ref "LED30") (pin "1") (pinfunction "CGREEN_1") (pintype "passive"))
      (node (ref "LED31") (pin "1") (pinfunction "CGREEN_1") (pintype "passive"))
      (node (ref "LED32") (pin "1") (pinfunction "CGREEN_1") (pintype "passive"))
      (node (ref "R36") (pin "1") (pinfunction "1_1") (pintype "passive"))
    )
    (net (code "12") (name "COLB4_SIG") (class "Default")
      (node (ref "Q24") (pin "1") (pinfunction "B_1") (pintype "passive"))
      (node (ref "U1") (pin "14") (pinfunction "PB4_14") (pintype "bidirectional"))
    )
    (net (code "13") (name "COLB5") (class "Default")
      (node (ref "LED33") (pin "1") (pinfunction "CGREEN_1") (pintype "passive"))
      (node (ref "LED34") (pin "1") (pinfunction "CGREEN_1") (pintype "passive"))
      (node (ref "LED35") (pin "1") (pinfunction "CGREEN_1") (pintype "passive"))
      (node (ref "LED36") (pin "1") (pinfunction "CGREEN_1") (pintype "passive"))
      (node (ref "LED37") (pin "1") (pinfunction "CGREEN_1") (pintype "passive"))
      (node (ref "LED38") (pin "1") (pinfunction "CGREEN_1") (pintype "passive"))
      (node (ref "LED39") (pin "1") (pinfunction "CGREEN_1") (pintype "passive"))
      (node (ref "LED40") (pin "1") (pinfunction "CGREEN_1") (pintype "passive"))
      (node (ref "R31") (pin "1") (pinfunction "1_1") (pintype "passive"))
    )
    (net (code "14") (name "COLB5_SIG") (class "Default")
      (node (ref "Q19") (pin "1") (pinfunction "B_1") (pintype "passive"))
      (node (ref "U1") (pin "11") (pinfunction "PB1(SCK)_11") (pintype "bidirectional"))
    )
    (net (code "15") (name "COLB6") (class "Default")
      (node (ref "LED41") (pin "1") (pinfunction "CGREEN_1") (pintype "passive"))
      (node (ref "LED42") (pin "1") (pinfunction "CGREEN_1") (pintype "passive"))
      (node (ref "LED43") (pin "1") (pinfunction "CGREEN_1") (pintype "passive"))
      (node (ref "LED44") (pin "1") (pinfunction "CGREEN_1") (pintype "passive"))
      (node (ref "LED45") (pin "1") (pinfunction "CGREEN_1") (pintype "passive"))
      (node (ref "LED46") (pin "1") (pinfunction "CGREEN_1") (pintype "passive"))
      (node (ref "LED47") (pin "1") (pinfunction "CGREEN_1") (pintype "passive"))
      (node (ref "LED48") (pin "1") (pinfunction "CGREEN_1") (pintype "passive"))
      (node (ref "R42") (pin "1") (pinfunction "1_1") (pintype "passive"))
    )
    (net (code "16") (name "COLB6_SIG") (class "Default")
      (node (ref "Q30") (pin "1") (pinfunction "B_1") (pintype "passive"))
      (node (ref "U1") (pin "45") (pinfunction "PA6_45") (pintype "bidirectional"))
    )
    (net (code "17") (name "COLB7") (class "Default")
      (node (ref "LED49") (pin "1") (pinfunction "CGREEN_1") (pintype "passive"))
      (node (ref "LED50") (pin "1") (pinfunction "CGREEN_1") (pintype "passive"))
      (node (ref "LED51") (pin "1") (pinfunction "CGREEN_1") (pintype "passive"))
      (node (ref "LED52") (pin "1") (pinfunction "CGREEN_1") (pintype "passive"))
      (node (ref "LED53") (pin "1") (pinfunction "CGREEN_1") (pintype "passive"))
      (node (ref "LED54") (pin "1") (pinfunction "CGREEN_1") (pintype "passive"))
      (node (ref "LED55") (pin "1") (pinfunction "CGREEN_1") (pintype "passive"))
      (node (ref "LED56") (pin "1") (pinfunction "CGREEN_1") (pintype "passive"))
      (node (ref "R37") (pin "1") (pinfunction "1_1") (pintype "passive"))
    )
    (net (code "18") (name "COLB7_SIG") (class "Default")
      (node (ref "Q25") (pin "1") (pinfunction "B_1") (pintype "passive"))
      (node (ref "U1") (pin "48") (pinfunction "PA3_48") (pintype "bidirectional"))
    )
    (net (code "19") (name "COLB8") (class "Default")
      (node (ref "LED57") (pin "1") (pinfunction "CGREEN_1") (pintype "passive"))
      (node (ref "LED58") (pin "1") (pinfunction "CGREEN_1") (pintype "passive"))
      (node (ref "LED59") (pin "1") (pinfunction "CGREEN_1") (pintype "passive"))
      (node (ref "LED60") (pin "1") (pinfunction "CGREEN_1") (pintype "passive"))
      (node (ref "LED61") (pin "1") (pinfunction "CGREEN_1") (pintype "passive"))
      (node (ref "LED62") (pin "1") (pinfunction "CGREEN_1") (pintype "passive"))
      (node (ref "LED63") (pin "1") (pinfunction "CGREEN_1") (pintype "passive"))
      (node (ref "LED64") (pin "1") (pinfunction "CGREEN_1") (pintype "passive"))
      (node (ref "R40") (pin "1") (pinfunction "1_1") (pintype "passive"))
    )
    (net (code "20") (name "COLB8_SIG") (class "Default")
      (node (ref "Q28") (pin "1") (pinfunction "B_1") (pintype "passive"))
      (node (ref "U1") (pin "51") (pinfunction "PA0_51") (pintype "bidirectional"))
    )
    (net (code "21") (name "COLG1") (class "Default")
      (node (ref "LED1") (pin "3") (pinfunction "CBLUE_3") (pintype "passive"))
      (node (ref "LED2") (pin "3") (pinfunction "CBLUE_3") (pintype "passive"))
      (node (ref "LED3") (pin "3") (pinfunction "CBLUE_3") (pintype "passive"))
      (node (ref "LED4") (pin "3") (pinfunction "CBLUE_3") (pintype "passive"))
      (node (ref "LED5") (pin "3") (pinfunction "CBLUE_3") (pintype "passive"))
      (node (ref "LED6") (pin "3") (pinfunction "CBLUE_3") (pintype "passive"))
      (node (ref "LED7") (pin "3") (pinfunction "CBLUE_3") (pintype "passive"))
      (node (ref "LED8") (pin "3") (pinfunction "CBLUE_3") (pintype "passive"))
      (node (ref "R26") (pin "1") (pinfunction "1_1") (pintype "passive"))
    )
    (net (code "22") (name "COLG1_SIG") (class "Default")
      (node (ref "Q14") (pin "1") (pinfunction "B_1") (pintype "passive"))
      (node (ref "U1") (pin "41") (pinfunction "PC6_41") (pintype "bidirectional"))
    )
    (net (code "23") (name "COLG2") (class "Default")
      (node (ref "LED10") (pin "3") (pinfunction "CBLUE_3") (pintype "passive"))
      (node (ref "LED11") (pin "3") (pinfunction "CBLUE_3") (pintype "passive"))
      (node (ref "LED12") (pin "3") (pinfunction "CBLUE_3") (pintype "passive"))
      (node (ref "LED13") (pin "3") (pinfunction "CBLUE_3") (pintype "passive"))
      (node (ref "LED14") (pin "3") (pinfunction "CBLUE_3") (pintype "passive"))
      (node (ref "LED15") (pin "3") (pinfunction "CBLUE_3") (pintype "passive"))
      (node (ref "LED16") (pin "3") (pinfunction "CBLUE_3") (pintype "passive"))
      (node (ref "LED9") (pin "3") (pinfunction "CBLUE_3") (pintype "passive"))
      (node (ref "R22") (pin "1") (pinfunction "1_1") (pintype "passive"))
    )
    (net (code "24") (name "COLG2_SIG") (class "Default")
      (node (ref "Q11") (pin "1") (pinfunction "B_1") (pintype "passive"))
      (node (ref "U1") (pin "38") (pinfunction "PC3_38") (pintype "bidirectional"))
    )
    (net (code "25") (name "COLG3") (class "Default")
      (node (ref "LED17") (pin "3") (pinfunction "CBLUE_3") (pintype "passive"))
      (node (ref "LED18") (pin "3") (pinfunction "CBLUE_3") (pintype "passive"))
      (node (ref "LED19") (pin "3") (pinfunction "CBLUE_3") (pintype "passive"))
      (node (ref "LED20") (pin "3") (pinfunction "CBLUE_3") (pintype "passive"))
      (node (ref "LED21") (pin "3") (pinfunction "CBLUE_3") (pintype "passive"))
      (node (ref "LED22") (pin "3") (pinfunction "CBLUE_3") (pintype "passive"))
      (node (ref "LED23") (pin "3") (pinfunction "CBLUE_3") (pintype "passive"))
      (node (ref "LED24") (pin "3") (pinfunction "CBLUE_3") (pintype "passive"))
      (node (ref "R24") (pin "1") (pinfunction "1_1") (pintype "passive"))
    )
    (net (code "26") (name "COLG3_SIG") (class "Default")
      (node (ref "Q12") (pin "1") (pinfunction "B_1") (pintype "passive"))
      (node (ref "U1") (pin "35") (pinfunction "PC0_35") (pintype "bidirectional"))
    )
    (net (code "27") (name "COLG4") (class "Default")
      (node (ref "LED25") (pin "3") (pinfunction "CBLUE_3") (pintype "passive"))
      (node (ref "LED26") (pin "3") (pinfunction "CBLUE_3") (pintype "passive"))
      (node (ref "LED27") (pin "3") (pinfunction "CBLUE_3") (pintype "passive"))
      (node (ref "LED28") (pin "3") (pinfunction "CBLUE_3") (pintype "passive"))
      (node (ref "LED29") (pin "3") (pinfunction "CBLUE_3") (pintype "passive"))
      (node (ref "LED30") (pin "3") (pinfunction "CBLUE_3") (pintype "passive"))
      (node (ref "LED31") (pin "3") (pinfunction "CBLUE_3") (pintype "passive"))
      (node (ref "LED32") (pin "3") (pinfunction "CBLUE_3") (pintype "passive"))
      (node (ref "R35") (pin "1") (pinfunction "1_1") (pintype "passive"))
    )
    (net (code "28") (name "COLG4_SIG") (class "Default")
      (node (ref "Q23") (pin "1") (pinfunction "B_1") (pintype "passive"))
      (node (ref "U1") (pin "15") (pinfunction "PB5_15") (pintype "bidirectional"))
    )
    (net (code "29") (name "COLG5") (class "Default")
      (node (ref "LED33") (pin "3") (pinfunction "CBLUE_3") (pintype "passive"))
      (node (ref "LED34") (pin "3") (pinfunction "CBLUE_3") (pintype "passive"))
      (node (ref "LED35") (pin "3") (pinfunction "CBLUE_3") (pintype "passive"))
      (node (ref "LED36") (pin "3") (pinfunction "CBLUE_3") (pintype "passive"))
      (node (ref "LED37") (pin "3") (pinfunction "CBLUE_3") (pintype "passive"))
      (node (ref "LED38") (pin "3") (pinfunction "CBLUE_3") (pintype "passive"))
      (node (ref "LED39") (pin "3") (pinfunction "CBLUE_3") (pintype "passive"))
      (node (ref "LED40") (pin "3") (pinfunction "CBLUE_3") (pintype "passive"))
      (node (ref "R30") (pin "1") (pinfunction "1_1") (pintype "passive"))
    )
    (net (code "30") (name "COLG5_SIG") (class "Default")
      (node (ref "Q18") (pin "1") (pinfunction "B_1") (pintype "passive"))
      (node (ref "U1") (pin "12") (pinfunction "PB2(MOSI)_12") (pintype "bidirectional"))
    )
    (net (code "31") (name "COLG6") (class "Default")
      (node (ref "LED41") (pin "3") (pinfunction "CBLUE_3") (pintype "passive"))
      (node (ref "LED42") (pin "3") (pinfunction "CBLUE_3") (pintype "passive"))
      (node (ref "LED43") (pin "3") (pinfunction "CBLUE_3") (pintype "passive"))
      (node (ref "LED44") (pin "3") (pinfunction "CBLUE_3") (pintype "passive"))
      (node (ref "LED45") (pin "3") (pinfunction "CBLUE_3") (pintype "passive"))
      (node (ref "LED46") (pin "3") (pinfunction "CBLUE_3") (pintype "passive"))
      (node (ref "LED47") (pin "3") (pinfunction "CBLUE_3") (pintype "passive"))
      (node (ref "LED48") (pin "3") (pinfunction "CBLUE_3") (pintype "passive"))
      (node (ref "R41") (pin "1") (pinfunction "1_1") (pintype "passive"))
    )
    (net (code "32") (name "COLG6_SIG") (class "Default")
      (node (ref "Q29") (pin "1") (pinfunction "B_1") (pintype "passive"))
      (node (ref "U1") (pin "44") (pinfunction "PA7_44") (pintype "bidirectional"))
    )
    (net (code "33") (name "COLG7") (class "Default")
      (node (ref "LED49") (pin "3") (pinfunction "CBLUE_3") (pintype "passive"))
      (node (ref "LED50") (pin "3") (pinfunction "CBLUE_3") (pintype "passive"))
      (node (ref "LED51") (pin "3") (pinfunction "CBLUE_3") (pintype "passive"))
      (node (ref "LED52") (pin "3") (pinfunction "CBLUE_3") (pintype "passive"))
      (node (ref "LED53") (pin "3") (pinfunction "CBLUE_3") (pintype "passive"))
      (node (ref "LED54") (pin "3") (pinfunction "CBLUE_3") (pintype "passive"))
      (node (ref "LED55") (pin "3") (pinfunction "CBLUE_3") (pintype "passive"))
      (node (ref "LED56") (pin "3") (pinfunction "CBLUE_3") (pintype "passive"))
      (node (ref "R44") (pin "1") (pinfunction "1_1") (pintype "passive"))
    )
    (net (code "34") (name "COLG7_SIG") (class "Default")
      (node (ref "Q32") (pin "1") (pinfunction "B_1") (pintype "passive"))
      (node (ref "U1") (pin "47") (pinfunction "PA4_47") (pintype "bidirectional"))
    )
    (net (code "35") (name "COLG8") (class "Default")
      (node (ref "LED57") (pin "3") (pinfunction "CBLUE_3") (pintype "passive"))
      (node (ref "LED58") (pin "3") (pinfunction "CBLUE_3") (pintype "passive"))
      (node (ref "LED59") (pin "3") (pinfunction "CBLUE_3") (pintype "passive"))
      (node (ref "LED60") (pin "3") (pinfunction "CBLUE_3") (pintype "passive"))
      (node (ref "LED61") (pin "3") (pinfunction "CBLUE_3") (pintype "passive"))
      (node (ref "LED62") (pin "3") (pinfunction "CBLUE_3") (pintype "passive"))
      (node (ref "LED63") (pin "3") (pinfunction "CBLUE_3") (pintype "passive"))
      (node (ref "LED64") (pin "3") (pinfunction "CBLUE_3") (pintype "passive"))
      (node (ref "R39") (pin "1") (pinfunction "1_1") (pintype "passive"))
    )
    (net (code "36") (name "COLG8_SIG") (class "Default")
      (node (ref "Q27") (pin "1") (pinfunction "B_1") (pintype "passive"))
      (node (ref "U1") (pin "50") (pinfunction "PA1_50") (pintype "bidirectional"))
    )
    (net (code "37") (name "COLR1") (class "Default")
      (node (ref "LED1") (pin "2") (pinfunction "CRED_2") (pintype "passive"))
      (node (ref "LED2") (pin "2") (pinfunction "CRED_2") (pintype "passive"))
      (node (ref "LED3") (pin "2") (pinfunction "CRED_2") (pintype "passive"))
      (node (ref "LED4") (pin "2") (pinfunction "CRED_2") (pintype "passive"))
      (node (ref "LED5") (pin "2") (pinfunction "CRED_2") (pintype "passive"))
      (node (ref "LED6") (pin "2") (pinfunction "CRED_2") (pintype "passive"))
      (node (ref "LED7") (pin "2") (pinfunction "CRED_2") (pintype "passive"))
      (node (ref "LED8") (pin "2") (pinfunction "CRED_2") (pintype "passive"))
      (node (ref "R25") (pin "1") (pinfunction "1_1") (pintype "passive"))
    )
    (net (code "38") (name "COLR1_SIG") (class "Default")
      (node (ref "Q13") (pin "1") (pinfunction "B_1") (pintype "passive"))
      (node (ref "U1") (pin "42") (pinfunction "PC7_42") (pintype "bidirectional"))
    )
    (net (code "39") (name "COLR2") (class "Default")
      (node (ref "LED10") (pin "2") (pinfunction "CRED_2") (pintype "passive"))
      (node (ref "LED11") (pin "2") (pinfunction "CRED_2") (pintype "passive"))
      (node (ref "LED12") (pin "2") (pinfunction "CRED_2") (pintype "passive"))
      (node (ref "LED13") (pin "2") (pinfunction "CRED_2") (pintype "passive"))
      (node (ref "LED14") (pin "2") (pinfunction "CRED_2") (pintype "passive"))
      (node (ref "LED15") (pin "2") (pinfunction "CRED_2") (pintype "passive"))
      (node (ref "LED16") (pin "2") (pinfunction "CRED_2") (pintype "passive"))
      (node (ref "LED9") (pin "2") (pinfunction "CRED_2") (pintype "passive"))
      (node (ref "R28") (pin "1") (pinfunction "1_1") (pintype "passive"))
    )
    (net (code "40") (name "COLR2_SIG") (class "Default")
      (node (ref "Q16") (pin "1") (pinfunction "B_1") (pintype "passive"))
      (node (ref "U1") (pin "39") (pinfunction "PC4_39") (pintype "bidirectional"))
    )
    (net (code "41") (name "COLR3") (class "Default")
      (node (ref "LED17") (pin "2") (pinfunction "CRED_2") (pintype "passive"))
      (node (ref "LED18") (pin "2") (pinfunction "CRED_2") (pintype "passive"))
      (node (ref "LED19") (pin "2") (pinfunction "CRED_2") (pintype "passive"))
      (node (ref "LED20") (pin "2") (pinfunction "CRED_2") (pintype "passive"))
      (node (ref "LED21") (pin "2") (pinfunction "CRED_2") (pintype "passive"))
      (node (ref "LED22") (pin "2") (pinfunction "CRED_2") (pintype "passive"))
      (node (ref "LED23") (pin "2") (pinfunction "CRED_2") (pintype "passive"))
      (node (ref "LED24") (pin "2") (pinfunction "CRED_2") (pintype "passive"))
      (node (ref "R23") (pin "1") (pinfunction "1_1") (pintype "passive"))
    )
    (net (code "42") (name "COLR3_SIG") (class "Default")
      (node (ref "Q4") (pin "1") (pinfunction "B_1") (pintype "passive"))
      (node (ref "U1") (pin "36") (pinfunction "PC1_36") (pintype "bidirectional"))
    )
    (net (code "43") (name "COLR4") (class "Default")
      (node (ref "LED25") (pin "2") (pinfunction "CRED_2") (pintype "passive"))
      (node (ref "LED26") (pin "2") (pinfunction "CRED_2") (pintype "passive"))
      (node (ref "LED27") (pin "2") (pinfunction "CRED_2") (pintype "passive"))
      (node (ref "LED28") (pin "2") (pinfunction "CRED_2") (pintype "passive"))
      (node (ref "LED29") (pin "2") (pinfunction "CRED_2") (pintype "passive"))
      (node (ref "LED30") (pin "2") (pinfunction "CRED_2") (pintype "passive"))
      (node (ref "LED31") (pin "2") (pinfunction "CRED_2") (pintype "passive"))
      (node (ref "LED32") (pin "2") (pinfunction "CRED_2") (pintype "passive"))
      (node (ref "R34") (pin "1") (pinfunction "1_1") (pintype "passive"))
    )
    (net (code "44") (name "COLR4_SIG") (class "Default")
      (node (ref "Q22") (pin "1") (pinfunction "B_1") (pintype "passive"))
      (node (ref "U1") (pin "16") (pinfunction "PB6_16") (pintype "bidirectional"))
    )
    (net (code "45") (name "COLR5") (class "Default")
      (node (ref "LED33") (pin "2") (pinfunction "CRED_2") (pintype "passive"))
      (node (ref "LED34") (pin "2") (pinfunction "CRED_2") (pintype "passive"))
      (node (ref "LED35") (pin "2") (pinfunction "CRED_2") (pintype "passive"))
      (node (ref "LED36") (pin "2") (pinfunction "CRED_2") (pintype "passive"))
      (node (ref "LED37") (pin "2") (pinfunction "CRED_2") (pintype "passive"))
      (node (ref "LED38") (pin "2") (pinfunction "CRED_2") (pintype "passive"))
      (node (ref "LED39") (pin "2") (pinfunction "CRED_2") (pintype "passive"))
      (node (ref "LED40") (pin "2") (pinfunction "CRED_2") (pintype "passive"))
      (node (ref "R29") (pin "1") (pinfunction "1_1") (pintype "passive"))
    )
    (net (code "46") (name "COLR5_SIG") (class "Default")
      (node (ref "Q17") (pin "1") (pinfunction "B_1") (pintype "passive"))
      (node (ref "U1") (pin "13") (pinfunction "PB3(MISO)_13") (pintype "bidirectional"))
    )
    (net (code "47") (name "COLR6") (class "Default")
      (node (ref "LED41") (pin "2") (pinfunction "CRED_2") (pintype "passive"))
      (node (ref "LED42") (pin "2") (pinfunction "CRED_2") (pintype "passive"))
      (node (ref "LED43") (pin "2") (pinfunction "CRED_2") (pintype "passive"))
      (node (ref "LED44") (pin "2") (pinfunction "CRED_2") (pintype "passive"))
      (node (ref "LED45") (pin "2") (pinfunction "CRED_2") (pintype "passive"))
      (node (ref "LED46") (pin "2") (pinfunction "CRED_2") (pintype "passive"))
      (node (ref "LED47") (pin "2") (pinfunction "CRED_2") (pintype "passive"))
      (node (ref "LED48") (pin "2") (pinfunction "CRED_2") (pintype "passive"))
      (node (ref "R32") (pin "1") (pinfunction "1_1") (pintype "passive"))
    )
    (net (code "48") (name "COLR6_SIG") (class "Default")
      (node (ref "Q20") (pin "1") (pinfunction "B_1") (pintype "passive"))
      (node (ref "U1") (pin "10") (pinfunction "PB0(SS)_10") (pintype "bidirectional"))
    )
    (net (code "49") (name "COLR7") (class "Default")
      (node (ref "LED49") (pin "2") (pinfunction "CRED_2") (pintype "passive"))
      (node (ref "LED50") (pin "2") (pinfunction "CRED_2") (pintype "passive"))
      (node (ref "LED51") (pin "2") (pinfunction "CRED_2") (pintype "passive"))
      (node (ref "LED52") (pin "2") (pinfunction "CRED_2") (pintype "passive"))
      (node (ref "LED53") (pin "2") (pinfunction "CRED_2") (pintype "passive"))
      (node (ref "LED54") (pin "2") (pinfunction "CRED_2") (pintype "passive"))
      (node (ref "LED55") (pin "2") (pinfunction "CRED_2") (pintype "passive"))
      (node (ref "LED56") (pin "2") (pinfunction "CRED_2") (pintype "passive"))
      (node (ref "R43") (pin "1") (pinfunction "1_1") (pintype "passive"))
    )
    (net (code "50") (name "COLR7_SIG") (class "Default")
      (node (ref "Q31") (pin "1") (pinfunction "B_1") (pintype "passive"))
      (node (ref "U1") (pin "46") (pinfunction "PA5_46") (pintype "bidirectional"))
    )
    (net (code "51") (name "COLR8") (class "Default")
      (node (ref "LED57") (pin "2") (pinfunction "CRED_2") (pintype "passive"))
      (node (ref "LED58") (pin "2") (pinfunction "CRED_2") (pintype "passive"))
      (node (ref "LED59") (pin "2") (pinfunction "CRED_2") (pintype "passive"))
      (node (ref "LED60") (pin "2") (pinfunction "CRED_2") (pintype "passive"))
      (node (ref "LED61") (pin "2") (pinfunction "CRED_2") (pintype "passive"))
      (node (ref "LED62") (pin "2") (pinfunction "CRED_2") (pintype "passive"))
      (node (ref "LED63") (pin "2") (pinfunction "CRED_2") (pintype "passive"))
      (node (ref "LED64") (pin "2") (pinfunction "CRED_2") (pintype "passive"))
      (node (ref "R38") (pin "1") (pinfunction "1_1") (pintype "passive"))
    )
    (net (code "52") (name "COLR8_SIG") (class "Default")
      (node (ref "Q26") (pin "1") (pinfunction "B_1") (pintype "passive"))
      (node (ref "U1") (pin "49") (pinfunction "PA2_49") (pintype "bidirectional"))
    )
    (net (code "53") (name "GND") (class "Default")
      (node (ref "C1") (pin "1") (pinfunction "1_1") (pintype "passive"))
      (node (ref "C2") (pin "1") (pinfunction "1_1") (pintype "passive"))
      (node (ref "C3") (pin "1") (pinfunction "1_1") (pintype "passive"))
      (node (ref "C4") (pin "1") (pinfunction "1_1") (pintype "passive"))
      (node (ref "C7") (pin "1") (pinfunction "1_1") (pintype "passive"))
      (node (ref "C8") (pin "1") (pinfunction "1_1") (pintype "passive"))
      (node (ref "Q1") (pin "2") (pinfunction "S_2") (pintype "passive"))
      (node (ref "Q10") (pin "2") (pinfunction "S_2") (pintype "passive"))
      (node (ref "Q11") (pin "3") (pinfunction "C_3") (pintype "passive"))
      (node (ref "Q12") (pin "3") (pinfunction "C_3") (pintype "passive"))
      (node (ref "Q13") (pin "3") (pinfunction "C_3") (pintype "passive"))
      (node (ref "Q14") (pin "3") (pinfunction "C_3") (pintype "passive"))
      (node (ref "Q15") (pin "3") (pinfunction "C_3") (pintype "passive"))
      (node (ref "Q16") (pin "3") (pinfunction "C_3") (pintype "passive"))
      (node (ref "Q17") (pin "3") (pinfunction "C_3") (pintype "passive"))
      (node (ref "Q18") (pin "3") (pinfunction "C_3") (pintype "passive"))
      (node (ref "Q19") (pin "3") (pinfunction "C_3") (pintype "passive"))
      (node (ref "Q2") (pin "2") (pinfunction "S_2") (pintype "passive"))
      (node (ref "Q20") (pin "3") (pinfunction "C_3") (pintype "passive"))
      (node (ref "Q21") (pin "3") (pinfunction "C_3") (pintype "passive"))
      (node (ref "Q22") (pin "3") (pinfunction "C_3") (pintype "passive"))
      (node (ref "Q23") (pin "3") (pinfunction "C_3") (pintype "passive"))
      (node (ref "Q24") (pin "3") (pinfunction "C_3") (pintype "passive"))
      (node (ref "Q25") (pin "3") (pinfunction "C_3") (pintype "passive"))
      (node (ref "Q26") (pin "3") (pinfunction "C_3") (pintype "passive"))
      (node (ref "Q27") (pin "3") (pinfunction "C_3") (pintype "passive"))
      (node (ref "Q28") (pin "3") (pinfunction "C_3") (pintype "passive"))
      (node (ref "Q29") (pin "3") (pinfunction "C_3") (pintype "passive"))
      (node (ref "Q3") (pin "3") (pinfunction "C_3") (pintype "passive"))
      (node (ref "Q30") (pin "3") (pinfunction "C_3") (pintype "passive"))
      (node (ref "Q31") (pin "3") (pinfunction "C_3") (pintype "passive"))
      (node (ref "Q32") (pin "3") (pinfunction "C_3") (pintype "passive"))
      (node (ref "Q4") (pin "3") (pinfunction "C_3") (pintype "passive"))
      (node (ref "Q5") (pin "2") (pinfunction "S_2") (pintype "passive"))
      (node (ref "Q6") (pin "2") (pinfunction "S_2") (pintype "passive"))
      (node (ref "Q7") (pin "2") (pinfunction "S_2") (pintype "passive"))
      (node (ref "Q8") (pin "2") (pinfunction "S_2") (pintype "passive"))
      (node (ref "Q9") (pin "2") (pinfunction "S_2") (pintype "passive"))
      (node (ref "R11") (pin "1") (pinfunction "1_1") (pintype "passive"))
      (node (ref "R13") (pin "1") (pinfunction "1_1") (pintype "passive"))
      (node (ref "R15") (pin "1") (pinfunction "1_1") (pintype "passive"))
      (node (ref "R17") (pin "1") (pinfunction "1_1") (pintype "passive"))
      (node (ref "R19") (pin "1") (pinfunction "1_1") (pintype "passive"))
      (node (ref "R21") (pin "1") (pinfunction "1_1") (pintype "passive"))
      (node (ref "R4") (pin "1") (pinfunction "1_1") (pintype "passive"))
      (node (ref "R5") (pin "1") (pinfunction "1_1") (pintype "passive"))
      (node (ref "U1") (pin "22") (pinfunction "GND_22") (pintype "bidirectional"))
      (node (ref "U1") (pin "53") (pinfunction "GND_53") (pintype "bidirectional"))
      (node (ref "U2") (pin "18") (pinfunction "GND2_18") (pintype "power_in"))
      (node (ref "U2") (pin "21") (pinfunction "GND3_21") (pintype "power_in"))
      (node (ref "U2") (pin "25") (pinfunction "AGND_25") (pintype "power_in"))
      (node (ref "U2") (pin "7") (pinfunction "GND1_7") (pintype "power_in"))
      (node (ref "U3") (pin "VBUS1") (pinfunction "VBUS_VBUS1") (pintype "bidirectional"))
    )
    (net (code "54") (name "Net-(D1-PadC)") (class "Default")
      (node (ref "D1") (pin "C") (pinfunction "C_C") (pintype "passive"))
      (node (ref "R94") (pin "1") (pinfunction "1_1") (pintype "passive"))
    )
    (net (code "55") (name "Net-(D2-PadC)") (class "Default")
      (node (ref "D2") (pin "C") (pinfunction "C_C") (pintype "passive"))
      (node (ref "R95") (pin "1") (pinfunction "1_1") (pintype "passive"))
    )
    (net (code "56") (name "Net-(Q1-D)") (class "Default")
      (node (ref "Q1") (pin "3") (pinfunction "D_3") (pintype "passive"))
      (node (ref "R1") (pin "1") (pinfunction "1_1") (pintype "passive"))
    )
    (net (code "57") (name "Net-(Q2-D)") (class "Default")
      (node (ref "Q2") (pin "3") (pinfunction "D_3") (pintype "passive"))
      (node (ref "R2") (pin "1") (pinfunction "1_1") (pintype "passive"))
    )
    (net (code "58") (name "Net-(Q3-E)") (class "Default")
      (node (ref "Q3") (pin "2") (pinfunction "E_2") (pintype "passive"))
      (node (ref "R3") (pin "2") (pinfunction "2_2") (pintype "passive"))
    )
    (net (code "59") (name "Net-(Q4-E)") (class "Default")
      (node (ref "Q4") (pin "2") (pinfunction "E_2") (pintype "passive"))
      (node (ref "R23") (pin "2") (pinfunction "2_2") (pintype "passive"))
    )
    (net (code "60") (name "Net-(Q5-D)") (class "Default")
      (node (ref "Q5") (pin "3") (pinfunction "D_3") (pintype "passive"))
      (node (ref "R10") (pin "1") (pinfunction "1_1") (pintype "passive"))
    )
    (net (code "61") (name "Net-(Q6-D)") (class "Default")
      (node (ref "Q6") (pin "3") (pinfunction "D_3") (pintype "passive"))
      (node (ref "R12") (pin "1") (pinfunction "1_1") (pintype "passive"))
    )
    (net (code "62") (name "Net-(Q7-D)") (class "Default")
      (node (ref "Q7") (pin "3") (pinfunction "D_3") (pintype "passive"))
      (node (ref "R14") (pin "1") (pinfunction "1_1") (pintype "passive"))
    )
    (net (code "63") (name "Net-(Q8-D)") (class "Default")
      (node (ref "Q8") (pin "3") (pinfunction "D_3") (pintype "passive"))
      (node (ref "R16") (pin "1") (pinfunction "1_1") (pintype "passive"))
    )
    (net (code "64") (name "Net-(Q9-D)") (class "Default")
      (node (ref "Q9") (pin "3") (pinfunction "D_3") (pintype "passive"))
      (node (ref "R18") (pin "1") (pinfunction "1_1") (pintype "passive"))
    )
    (net (code "65") (name "Net-(Q10-D)") (class "Default")
      (node (ref "Q10") (pin "3") (pinfunction "D_3") (pintype "passive"))
      (node (ref "R20") (pin "1") (pinfunction "1_1") (pintype "passive"))
    )
    (net (code "66") (name "Net-(Q11-E)") (class "Default")
      (node (ref "Q11") (pin "2") (pinfunction "E_2") (pintype "passive"))
      (node (ref "R22") (pin "2") (pinfunction "2_2") (pintype "passive"))
    )
    (net (code "67") (name "Net-(Q12-E)") (class "Default")
      (node (ref "Q12") (pin "2") (pinfunction "E_2") (pintype "passive"))
      (node (ref "R24") (pin "2") (pinfunction "2_2") (pintype "passive"))
    )
    (net (code "68") (name "Net-(Q13-E)") (class "Default")
      (node (ref "Q13") (pin "2") (pinfunction "E_2") (pintype "passive"))
      (node (ref "R25") (pin "2") (pinfunction "2_2") (pintype "passive"))
    )
    (net (code "69") (name "Net-(Q14-E)") (class "Default")
      (node (ref "Q14") (pin "2") (pinfunction "E_2") (pintype "passive"))
      (node (ref "R26") (pin "2") (pinfunction "2_2") (pintype "passive"))
    )
    (net (code "70") (name "Net-(Q15-E)") (class "Default")
      (node (ref "Q15") (pin "2") (pinfunction "E_2") (pintype "passive"))
      (node (ref "R27") (pin "2") (pinfunction "2_2") (pintype "passive"))
    )
    (net (code "71") (name "Net-(Q16-E)") (class "Default")
      (node (ref "Q16") (pin "2") (pinfunction "E_2") (pintype "passive"))
      (node (ref "R28") (pin "2") (pinfunction "2_2") (pintype "passive"))
    )
    (net (code "72") (name "Net-(Q17-E)") (class "Default")
      (node (ref "Q17") (pin "2") (pinfunction "E_2") (pintype "passive"))
      (node (ref "R29") (pin "2") (pinfunction "2_2") (pintype "passive"))
    )
    (net (code "73") (name "Net-(Q18-E)") (class "Default")
      (node (ref "Q18") (pin "2") (pinfunction "E_2") (pintype "passive"))
      (node (ref "R30") (pin "2") (pinfunction "2_2") (pintype "passive"))
    )
    (net (code "74") (name "Net-(Q19-E)") (class "Default")
      (node (ref "Q19") (pin "2") (pinfunction "E_2") (pintype "passive"))
      (node (ref "R31") (pin "2") (pinfunction "2_2") (pintype "passive"))
    )
    (net (code "75") (name "Net-(Q20-E)") (class "Default")
      (node (ref "Q20") (pin "2") (pinfunction "E_2") (pintype "passive"))
      (node (ref "R32") (pin "2") (pinfunction "2_2") (pintype "passive"))
    )
    (net (code "76") (name "Net-(Q21-E)") (class "Default")
      (node (ref "Q21") (pin "2") (pinfunction "E_2") (pintype "passive"))
      (node (ref "R33") (pin "2") (pinfunction "2_2") (pintype "passive"))
    )
    (net (code "77") (name "Net-(Q22-E)") (class "Default")
      (node (ref "Q22") (pin "2") (pinfunction "E_2") (pintype "passive"))
      (node (ref "R34") (pin "2") (pinfunction "2_2") (pintype "passive"))
    )
    (net (code "78") (name "Net-(Q23-E)") (class "Default")
      (node (ref "Q23") (pin "2") (pinfunction "E_2") (pintype "passive"))
      (node (ref "R35") (pin "2") (pinfunction "2_2") (pintype "passive"))
    )
    (net (code "79") (name "Net-(Q24-E)") (class "Default")
      (node (ref "Q24") (pin "2") (pinfunction "E_2") (pintype "passive"))
      (node (ref "R36") (pin "2") (pinfunction "2_2") (pintype "passive"))
    )
    (net (code "80") (name "Net-(Q25-E)") (class "Default")
      (node (ref "Q25") (pin "2") (pinfunction "E_2") (pintype "passive"))
      (node (ref "R37") (pin "2") (pinfunction "2_2") (pintype "passive"))
    )
    (net (code "81") (name "Net-(Q26-E)") (class "Default")
      (node (ref "Q26") (pin "2") (pinfunction "E_2") (pintype "passive"))
      (node (ref "R38") (pin "2") (pinfunction "2_2") (pintype "passive"))
    )
    (net (code "82") (name "Net-(Q27-E)") (class "Default")
      (node (ref "Q27") (pin "2") (pinfunction "E_2") (pintype "passive"))
      (node (ref "R39") (pin "2") (pinfunction "2_2") (pintype "passive"))
    )
    (net (code "83") (name "Net-(Q28-E)") (class "Default")
      (node (ref "Q28") (pin "2") (pinfunction "E_2") (pintype "passive"))
      (node (ref "R40") (pin "2") (pinfunction "2_2") (pintype "passive"))
    )
    (net (code "84") (name "Net-(Q29-E)") (class "Default")
      (node (ref "Q29") (pin "2") (pinfunction "E_2") (pintype "passive"))
      (node (ref "R41") (pin "2") (pinfunction "2_2") (pintype "passive"))
    )
    (net (code "85") (name "Net-(Q30-E)") (class "Default")
      (node (ref "Q30") (pin "2") (pinfunction "E_2") (pintype "passive"))
      (node (ref "R42") (pin "2") (pinfunction "2_2") (pintype "passive"))
    )
    (net (code "86") (name "Net-(Q31-E)") (class "Default")
      (node (ref "Q31") (pin "2") (pinfunction "E_2") (pintype "passive"))
      (node (ref "R43") (pin "2") (pinfunction "2_2") (pintype "passive"))
    )
    (net (code "87") (name "Net-(Q32-E)") (class "Default")
      (node (ref "Q32") (pin "2") (pinfunction "E_2") (pintype "passive"))
      (node (ref "R44") (pin "2") (pinfunction "2_2") (pintype "passive"))
    )
    (net (code "88") (name "Net-(U1-XTAL1)") (class "Default")
      (node (ref "C8") (pin "2") (pinfunction "2_2") (pintype "passive"))
      (node (ref "TP2") (pin "TP") (pinfunction "TP_TP") (pintype "input"))
      (node (ref "U1") (pin "24") (pinfunction "XTAL1_24") (pintype "bidirectional"))
      (node (ref "X2") (pin "1") (pinfunction "1_1") (pintype "passive"))
    )
    (net (code "89") (name "Net-(U1-XTAL2)") (class "Default")
      (node (ref "C7") (pin "2") (pinfunction "2_2") (pintype "passive"))
      (node (ref "U1") (pin "23") (pinfunction "XTAL2_23") (pintype "bidirectional"))
      (node (ref "X2") (pin "2") (pinfunction "2_2") (pintype "passive"))
    )
    (net (code "90") (name "Net-(U2-RXLED)") (class "Default")
      (node (ref "R94") (pin "2") (pinfunction "2_2") (pintype "passive"))
      (node (ref "U2") (pin "22") (pinfunction "RXLED_22") (pintype "bidirectional"))
    )
    (net (code "91") (name "Net-(U2-TXLED)") (class "Default")
      (node (ref "R95") (pin "2") (pinfunction "2_2") (pintype "passive"))
      (node (ref "U2") (pin "23") (pinfunction "TXLED_23") (pintype "bidirectional"))
    )
    (net (code "92") (name "Net-(U3-GND)") (class "Default")
      (node (ref "F1") (pin "1") (pinfunction "1_1") (pintype "passive"))
      (node (ref "U3") (pin "GND1") (pinfunction "GND_GND1") (pintype "bidirectional"))
    )
    (net (code "93") (name "ROW2") (class "Default")
      (node (ref "LED10") (pin "4") (pinfunction "A_4") (pintype "passive"))
      (node (ref "LED18") (pin "4") (pinfunction "A_4") (pintype "passive"))
      (node (ref "LED2") (pin "4") (pinfunction "A_4") (pintype "passive"))
      (node (ref "LED26") (pin "4") (pinfunction "A_4") (pintype "passive"))
      (node (ref "LED34") (pin "4") (pinfunction "A_4") (pintype "passive"))
      (node (ref "LED42") (pin "4") (pinfunction "A_4") (pintype "passive"))
      (node (ref "LED50") (pin "4") (pinfunction "A_4") (pintype "passive"))
      (node (ref "LED58") (pin "4") (pinfunction "A_4") (pintype "passive"))
      (node (ref "R2") (pin "2") (pinfunction "2_2") (pintype "passive"))
    )
    (net (code "94") (name "ROW3") (class "Default")
      (node (ref "LED11") (pin "4") (pinfunction "A_4") (pintype "passive"))
      (node (ref "LED19") (pin "4") (pinfunction "A_4") (pintype "passive"))
      (node (ref "LED27") (pin "4") (pinfunction "A_4") (pintype "passive"))
      (node (ref "LED3") (pin "4") (pinfunction "A_4") (pintype "passive"))
      (node (ref "LED35") (pin "4") (pinfunction "A_4") (pintype "passive"))
      (node (ref "LED43") (pin "4") (pinfunction "A_4") (pintype "passive"))
      (node (ref "LED51") (pin "4") (pinfunction "A_4") (pintype "passive"))
      (node (ref "LED59") (pin "4") (pinfunction "A_4") (pintype "passive"))
      (node (ref "R10") (pin "2") (pinfunction "2_2") (pintype "passive"))
    )
    (net (code "95") (name "ROW4") (class "Default")
      (node (ref "LED12") (pin "4") (pinfunction "A_4") (pintype "passive"))
      (node (ref "LED20") (pin "4") (pinfunction "A_4") (pintype "passive"))
      (node (ref "LED28") (pin "4") (pinfunction "A_4") (pintype "passive"))
      (node (ref "LED36") (pin "4") (pinfunction "A_4") (pintype "passive"))
      (node (ref "LED4") (pin "4") (pinfunction "A_4") (pintype "passive"))
      (node (ref "LED44") (pin "4") (pinfunction "A_4") (pintype "passive"))
      (node (ref "LED52") (pin "4") (pinfunction "A_4") (pintype "passive"))
      (node (ref "LED60") (pin "4") (pinfunction "A_4") (pintype "passive"))
      (node (ref "R12") (pin "2") (pinfunction "2_2") (pintype "passive"))
    )
    (net (code "96") (name "ROW5") (class "Default")
      (node (ref "LED13") (pin "4") (pinfunction "A_4") (pintype "passive"))
      (node (ref "LED21") (pin "4") (pinfunction "A_4") (pintype "passive"))
      (node (ref "LED29") (pin "4") (pinfunction "A_4") (pintype "passive"))
      (node (ref "LED37") (pin "4") (pinfunction "A_4") (pintype "passive"))
      (node (ref "LED45") (pin "4") (pinfunction "A_4") (pintype "passive"))
      (node (ref "LED5") (pin "4") (pinfunction "A_4") (pintype "passive"))
      (node (ref "LED53") (pin "4") (pinfunction "A_4") (pintype "passive"))
      (node (ref "LED61") (pin "4") (pinfunction "A_4") (pintype "passive"))
      (node (ref "R14") (pin "2") (pinfunction "2_2") (pintype "passive"))
    )
    (net (code "97") (name "ROW6") (class "Default")
      (node (ref "LED14") (pin "4") (pinfunction "A_4") (pintype "passive"))
      (node (ref "LED22") (pin "4") (pinfunction "A_4") (pintype "passive"))
      (node (ref "LED30") (pin "4") (pinfunction "A_4") (pintype "passive"))
      (node (ref "LED38") (pin "4") (pinfunction "A_4") (pintype "passive"))
      (node (ref "LED46") (pin "4") (pinfunction "A_4") (pintype "passive"))
      (node (ref "LED54") (pin "4") (pinfunction "A_4") (pintype "passive"))
      (node (ref "LED6") (pin "4") (pinfunction "A_4") (pintype "passive"))
      (node (ref "LED62") (pin "4") (pinfunction "A_4") (pintype "passive"))
      (node (ref "R16") (pin "2") (pinfunction "2_2") (pintype "passive"))
    )
    (net (code "98") (name "ROW7") (class "Default")
      (node (ref "LED15") (pin "4") (pinfunction "A_4") (pintype "passive"))
      (node (ref "LED23") (pin "4") (pinfunction "A_4") (pintype "passive"))
      (node (ref "LED31") (pin "4") (pinfunction "A_4") (pintype "passive"))
      (node (ref "LED39") (pin "4") (pinfunction "A_4") (pintype "passive"))
      (node (ref "LED47") (pin "4") (pinfunction "A_4") (pintype "passive"))
      (node (ref "LED55") (pin "4") (pinfunction "A_4") (pintype "passive"))
      (node (ref "LED63") (pin "4") (pinfunction "A_4") (pintype "passive"))
      (node (ref "LED7") (pin "4") (pinfunction "A_4") (pintype "passive"))
      (node (ref "R18") (pin "2") (pinfunction "2_2") (pintype "passive"))
    )
    (net (code "99") (name "ROW8") (class "Default")
      (node (ref "LED16") (pin "4") (pinfunction "A_4") (pintype "passive"))
      (node (ref "LED24") (pin "4") (pinfunction "A_4") (pintype "passive"))
      (node (ref "LED32") (pin "4") (pinfunction "A_4") (pintype "passive"))
      (node (ref "LED40") (pin "4") (pinfunction "A_4") (pintype "passive"))
      (node (ref "LED48") (pin "4") (pinfunction "A_4") (pintype "passive"))
      (node (ref "LED56") (pin "4") (pinfunction "A_4") (pintype "passive"))
      (node (ref "LED64") (pin "4") (pinfunction "A_4") (pintype "passive"))
      (node (ref "LED8") (pin "4") (pinfunction "A_4") (pintype "passive"))
      (node (ref "R20") (pin "2") (pinfunction "2_2") (pintype "passive"))
    )
    (net (code "100") (name "ROW_SIG2") (class "Default")
      (node (ref "Q2") (pin "1") (pinfunction "G_1") (pintype "passive"))
      (node (ref "R5") (pin "2") (pinfunction "2_2") (pintype "passive"))
      (node (ref "U1") (pin "26") (pinfunction "PD1(SDA)_26") (pintype "bidirectional"))
    )
    (net (code "101") (name "ROW_SIG3") (class "Default")
      (node (ref "Q5") (pin "1") (pinfunction "G_1") (pintype "passive"))
      (node (ref "R11") (pin "2") (pinfunction "2_2") (pintype "passive"))
      (node (ref "U1") (pin "27") (pinfunction "PD2_27") (pintype "bidirectional"))
    )
    (net (code "102") (name "ROW_SIG4") (class "Default")
      (node (ref "Q6") (pin "1") (pinfunction "G_1") (pintype "passive"))
      (node (ref "R13") (pin "2") (pinfunction "2_2") (pintype "passive"))
      (node (ref "U1") (pin "28") (pinfunction "PD3_28") (pintype "bidirectional"))
    )
    (net (code "103") (name "ROW_SIG5") (class "Default")
      (node (ref "Q7") (pin "1") (pinfunction "G_1") (pintype "passive"))
      (node (ref "R15") (pin "2") (pinfunction "2_2") (pintype "passive"))
      (node (ref "U1") (pin "29") (pinfunction "PD4_29") (pintype "bidirectional"))
    )
    (net (code "104") (name "ROW_SIG6") (class "Default")
      (node (ref "Q8") (pin "1") (pinfunction "G_1") (pintype "passive"))
      (node (ref "R17") (pin "2") (pinfunction "2_2") (pintype "passive"))
      (node (ref "U1") (pin "30") (pinfunction "PD5_30") (pintype "bidirectional"))
    )
    (net (code "105") (name "ROW_SIG7") (class "Default")
      (node (ref "Q9") (pin "1") (pinfunction "G_1") (pintype "passive"))
      (node (ref "R19") (pin "2") (pinfunction "2_2") (pintype "passive"))
      (node (ref "U1") (pin "31") (pinfunction "PD6_31") (pintype "bidirectional"))
    )
    (net (code "106") (name "ROW_SIG8") (class "Default")
      (node (ref "Q10") (pin "1") (pinfunction "G_1") (pintype "passive"))
      (node (ref "R21") (pin "2") (pinfunction "2_2") (pintype "passive"))
      (node (ref "U1") (pin "32") (pinfunction "PD7_32") (pintype "bidirectional"))
    )
    (net (code "107") (name "RXD") (class "Default")
      (node (ref "U1") (pin "2") (pinfunction "PE0(RXD)_2") (pintype "bidirectional"))
      (node (ref "U2") (pin "5") (pinfunction "RXD_5") (pintype "input"))
    )
    (net (code "108") (name "TXD") (class "Default")
      (node (ref "U1") (pin "3") (pinfunction "PE1(TXD)_3") (pintype "bidirectional"))
      (node (ref "U2") (pin "1") (pinfunction "TXD_1") (pintype "output"))
    )
    (net (code "109") (name "USB_+") (class "Default")
      (node (ref "U2") (pin "15") (pinfunction "USBDP_15") (pintype "bidirectional"))
      (node (ref "U3") (pin "D+1") (pinfunction "D+_D+1") (pintype "bidirectional"))
      (node (ref "U4") (pin "29") (pinfunction "D+_29") (pintype "bidirectional"))
    )
    (net (code "110") (name "USB_-") (class "Default")
      (node (ref "U2") (pin "16") (pinfunction "USBDM_16") (pintype "bidirectional"))
      (node (ref "U3") (pin "D-1") (pinfunction "D-_D-1") (pintype "bidirectional"))
      (node (ref "U4") (pin "30") (pinfunction "D-_30") (pintype "bidirectional"))
    )
    (net (code "111") (name "VCC") (class "Default")
      (node (ref "C1") (pin "2") (pinfunction "2_2") (pintype "passive"))
      (node (ref "C2") (pin "2") (pinfunction "2_2") (pintype "passive"))
      (node (ref "C4") (pin "2") (pinfunction "2_2") (pintype "passive"))
      (node (ref "D1") (pin "A") (pinfunction "A_A") (pintype "passive"))
      (node (ref "D2") (pin "A") (pinfunction "A_A") (pintype "passive"))
      (node (ref "F1") (pin "2") (pinfunction "2_2") (pintype "passive"))
      (node (ref "U1") (pin "52") (pinfunction "VCC_52") (pintype "bidirectional"))
      (node (ref "U2") (pin "20") (pinfunction "VCC_20") (pintype "power_in"))
    )
    (net (code "112") (name "unconnected-(U1-AGND-Pad63)") (class "Default")
      (node (ref "U1") (pin "63") (pinfunction "AGND_63") (pintype "bidirectional"))
    )
    (net (code "113") (name "unconnected-(U1-AREF-Pad62)") (class "Default")
      (node (ref "U1") (pin "62") (pinfunction "AREF_62") (pintype "bidirectional"))
    )
    (net (code "114") (name "unconnected-(U1-AVCC-Pad64)") (class "Default")
      (node (ref "U1") (pin "64") (pinfunction "AVCC_64") (pintype "bidirectional"))
    )
    (net (code "115") (name "unconnected-(U1-PE2-Pad4)") (class "Default")
      (node (ref "U1") (pin "4") (pinfunction "PE2_4") (pintype "bidirectional"))
    )
    (net (code "116") (name "unconnected-(U1-PE3-Pad5)") (class "Default")
      (node (ref "U1") (pin "5") (pinfunction "PE3_5") (pintype "bidirectional"))
    )
    (net (code "117") (name "unconnected-(U1-PE4-Pad6)") (class "Default")
      (node (ref "U1") (pin "6") (pinfunction "PE4_6") (pintype "bidirectional"))
    )
    (net (code "118") (name "unconnected-(U1-PE5-Pad7)") (class "Default")
      (node (ref "U1") (pin "7") (pinfunction "PE5_7") (pintype "bidirectional"))
    )
    (net (code "119") (name "unconnected-(U1-PE6-Pad8)") (class "Default")
      (node (ref "U1") (pin "8") (pinfunction "PE6_8") (pintype "bidirectional"))
    )
    (net (code "120") (name "unconnected-(U1-PE7-Pad9)") (class "Default")
      (node (ref "U1") (pin "9") (pinfunction "PE7_9") (pintype "bidirectional"))
    )
    (net (code "121") (name "unconnected-(U1-PF0-Pad61)") (class "Default")
      (node (ref "U1") (pin "61") (pinfunction "PF0_61") (pintype "bidirectional"))
    )
    (net (code "122") (name "unconnected-(U1-PF1-Pad60)") (class "Default")
      (node (ref "U1") (pin "60") (pinfunction "PF1_60") (pintype "bidirectional"))
    )
    (net (code "123") (name "unconnected-(U1-PF2-Pad59)") (class "Default")
      (node (ref "U1") (pin "59") (pinfunction "PF2_59") (pintype "bidirectional"))
    )
    (net (code "124") (name "unconnected-(U1-PF3-Pad58)") (class "Default")
      (node (ref "U1") (pin "58") (pinfunction "PF3_58") (pintype "bidirectional"))
    )
    (net (code "125") (name "unconnected-(U1-PF4-Pad57)") (class "Default")
      (node (ref "U1") (pin "57") (pinfunction "PF4_57") (pintype "bidirectional"))
    )
    (net (code "126") (name "unconnected-(U1-PF5-Pad56)") (class "Default")
      (node (ref "U1") (pin "56") (pinfunction "PF5_56") (pintype "bidirectional"))
    )
    (net (code "127") (name "unconnected-(U1-PF6-Pad55)") (class "Default")
      (node (ref "U1") (pin "55") (pinfunction "PF6_55") (pintype "bidirectional"))
    )
    (net (code "128") (name "unconnected-(U1-PF7-Pad54)") (class "Default")
      (node (ref "U1") (pin "54") (pinfunction "PF7_54") (pintype "bidirectional"))
    )
    (net (code "129") (name "unconnected-(U1-PG0-Pad33)") (class "Default")
      (node (ref "U1") (pin "33") (pinfunction "PG0_33") (pintype "bidirectional"))
    )
    (net (code "130") (name "unconnected-(U1-PG1-Pad34)") (class "Default")
      (node (ref "U1") (pin "34") (pinfunction "PG1_34") (pintype "bidirectional"))
    )
    (net (code "131") (name "unconnected-(U1-PG2-Pad43)") (class "Default")
      (node (ref "U1") (pin "43") (pinfunction "PG2_43") (pintype "bidirectional"))
    )
    (net (code "132") (name "unconnected-(U1-PG3-Pad18)") (class "Default")
      (node (ref "U1") (pin "18") (pinfunction "PG3_18") (pintype "bidirectional"))
    )
    (net (code "133") (name "unconnected-(U1-PG4-Pad19)") (class "Default")
      (node (ref "U1") (pin "19") (pinfunction "PG4_19") (pintype "bidirectional"))
    )
    (net (code "134") (name "unconnected-(U1-PG5-Pad1)") (class "Default")
      (node (ref "U1") (pin "1") (pinfunction "PG5_1") (pintype "bidirectional"))
    )
    (net (code "135") (name "unconnected-(U1-RESET-Pad20)") (class "Default")
      (node (ref "U1") (pin "20") (pinfunction "RESET_20") (pintype "bidirectional"))
    )
    (net (code "136") (name "unconnected-(U1-VCC-Pad21)") (class "Default")
      (node (ref "U1") (pin "21") (pinfunction "VCC_21") (pintype "bidirectional"))
    )
    (net (code "137") (name "unconnected-(U2-CTS-Pad11)") (class "Default")
      (node (ref "U2") (pin "11") (pinfunction "CTS_11") (pintype "bidirectional"))
    )
    (net (code "138") (name "unconnected-(U2-DTR-Pad2)") (class "Default")
      (node (ref "U2") (pin "2") (pinfunction "DTR_2") (pintype "bidirectional"))
    )
    (net (code "139") (name "unconnected-(U2-RTS-Pad3)") (class "Default")
      (node (ref "U2") (pin "3") (pinfunction "RTS_3") (pintype "bidirectional"))
    )
    (net (code "140") (name "unconnected-(U2-TEST-Pad26)") (class "Default")
      (node (ref "U2") (pin "26") (pinfunction "TEST_26") (pintype "input"))
    )
    (net (code "141") (name "unconnected-(U2-VCCIO-Pad4)") (class "Default")
      (node (ref "U2") (pin "4") (pinfunction "VCCIO_4") (pintype "power_in"))
    )
    (net (code "142") (name "unconnected-(U3-USBID-PadID1)") (class "Default")
      (node (ref "U3") (pin "ID1") (pinfunction "USBID_ID1") (pintype "bidirectional"))
    )
    (net (code "143") (name "unconnected-(U4-AVCC-Pad32)") (class "Default")
      (node (ref "U4") (pin "32") (pinfunction "AVCC_32") (pintype "bidirectional"))
    )
    (net (code "144") (name "unconnected-(U4-GND-Pad3)") (class "Default")
      (node (ref "U4") (pin "3") (pinfunction "GND_3") (pintype "bidirectional"))
    )
    (net (code "145") (name "unconnected-(U4-PB0-Pad14)") (class "Default")
      (node (ref "U4") (pin "14") (pinfunction "PB0_14") (pintype "bidirectional"))
    )
    (net (code "146") (name "unconnected-(U4-PB1(SCK)-Pad15)") (class "Default")
      (node (ref "U4") (pin "15") (pinfunction "PB1(SCK)_15") (pintype "bidirectional"))
    )
    (net (code "147") (name "unconnected-(U4-PB2(MOSI)-Pad16)") (class "Default")
      (node (ref "U4") (pin "16") (pinfunction "PB2(MOSI)_16") (pintype "bidirectional"))
    )
    (net (code "148") (name "unconnected-(U4-PB3(MISO)-Pad17)") (class "Default")
      (node (ref "U4") (pin "17") (pinfunction "PB3(MISO)_17") (pintype "bidirectional"))
    )
    (net (code "149") (name "unconnected-(U4-PB4-Pad18)") (class "Default")
      (node (ref "U4") (pin "18") (pinfunction "PB4_18") (pintype "bidirectional"))
    )
    (net (code "150") (name "unconnected-(U4-PB5-Pad19)") (class "Default")
      (node (ref "U4") (pin "19") (pinfunction "PB5_19") (pintype "bidirectional"))
    )
    (net (code "151") (name "unconnected-(U4-PB6-Pad20)") (class "Default")
      (node (ref "U4") (pin "20") (pinfunction "PB6_20") (pintype "bidirectional"))
    )
    (net (code "152") (name "unconnected-(U4-PB7-Pad21)") (class "Default")
      (node (ref "U4") (pin "21") (pinfunction "PB7_21") (pintype "bidirectional"))
    )
    (net (code "153") (name "unconnected-(U4-PC2-Pad5)") (class "Default")
      (node (ref "U4") (pin "5") (pinfunction "PC2_5") (pintype "bidirectional"))
    )
    (net (code "154") (name "unconnected-(U4-PC4-Pad26)") (class "Default")
      (node (ref "U4") (pin "26") (pinfunction "PC4_26") (pintype "bidirectional"))
    )
    (net (code "155") (name "unconnected-(U4-PC5-Pad25)") (class "Default")
      (node (ref "U4") (pin "25") (pinfunction "PC5_25") (pintype "bidirectional"))
    )
    (net (code "156") (name "unconnected-(U4-PC6-Pad23)") (class "Default")
      (node (ref "U4") (pin "23") (pinfunction "PC6_23") (pintype "bidirectional"))
    )
    (net (code "157") (name "unconnected-(U4-PC7-Pad22)") (class "Default")
      (node (ref "U4") (pin "22") (pinfunction "PC7_22") (pintype "bidirectional"))
    )
    (net (code "158") (name "unconnected-(U4-PD0-Pad6)") (class "Default")
      (node (ref "U4") (pin "6") (pinfunction "PD0_6") (pintype "bidirectional"))
    )
    (net (code "159") (name "unconnected-(U4-PD1-Pad7)") (class "Default")
      (node (ref "U4") (pin "7") (pinfunction "PD1_7") (pintype "bidirectional"))
    )
    (net (code "160") (name "unconnected-(U4-PD2(RX)-Pad8)") (class "Default")
      (node (ref "U4") (pin "8") (pinfunction "PD2(RX)_8") (pintype "bidirectional"))
    )
    (net (code "161") (name "unconnected-(U4-PD3(TX)-Pad9)") (class "Default")
      (node (ref "U4") (pin "9") (pinfunction "PD3(TX)_9") (pintype "bidirectional"))
    )
    (net (code "162") (name "unconnected-(U4-PD4-Pad10)") (class "Default")
      (node (ref "U4") (pin "10") (pinfunction "PD4_10") (pintype "bidirectional"))
    )
    (net (code "163") (name "unconnected-(U4-PD5-Pad11)") (class "Default")
      (node (ref "U4") (pin "11") (pinfunction "PD5_11") (pintype "bidirectional"))
    )
    (net (code "164") (name "unconnected-(U4-PD6(RTS)-Pad12)") (class "Default")
      (node (ref "U4") (pin "12") (pinfunction "PD6(RTS)_12") (pintype "bidirectional"))
    )
    (net (code "165") (name "unconnected-(U4-PD7(CTS)-Pad13)") (class "Default")
      (node (ref "U4") (pin "13") (pinfunction "PD7(CTS)_13") (pintype "bidirectional"))
    )
    (net (code "166") (name "unconnected-(U4-RESET{slash}PC1-Pad24)") (class "Default")
      (node (ref "U4") (pin "24") (pinfunction "RESET/PC1_24") (pintype "bidirectional"))
    )
    (net (code "167") (name "unconnected-(U4-UCAP-Pad27)") (class "Default")
      (node (ref "U4") (pin "27") (pinfunction "UCAP_27") (pintype "bidirectional"))
    )
    (net (code "168") (name "unconnected-(U4-UGND-Pad28)") (class "Default")
      (node (ref "U4") (pin "28") (pinfunction "UGND_28") (pintype "bidirectional"))
    )
    (net (code "169") (name "unconnected-(U4-UVCC-Pad31)") (class "Default")
      (node (ref "U4") (pin "31") (pinfunction "UVCC_31") (pintype "bidirectional"))
    )
    (net (code "170") (name "unconnected-(U4-VCC-Pad4)") (class "Default")
      (node (ref "U4") (pin "4") (pinfunction "VCC_4") (pintype "bidirectional"))
    )
    (net (code "171") (name "unconnected-(U4-XTAL1-Pad1)") (class "Default")
      (node (ref "U4") (pin "1") (pinfunction "XTAL1_1") (pintype "bidirectional"))
    )
    (net (code "172") (name "unconnected-(U4-XTAL2{slash}PC0-Pad2)") (class "Default")
      (node (ref "U4") (pin "2") (pinfunction "XTAL2/PC0_2") (pintype "bidirectional"))
    )
  )
)
